# 20160428.net
KiCad netlist of a schematic drawn in Altium Designer
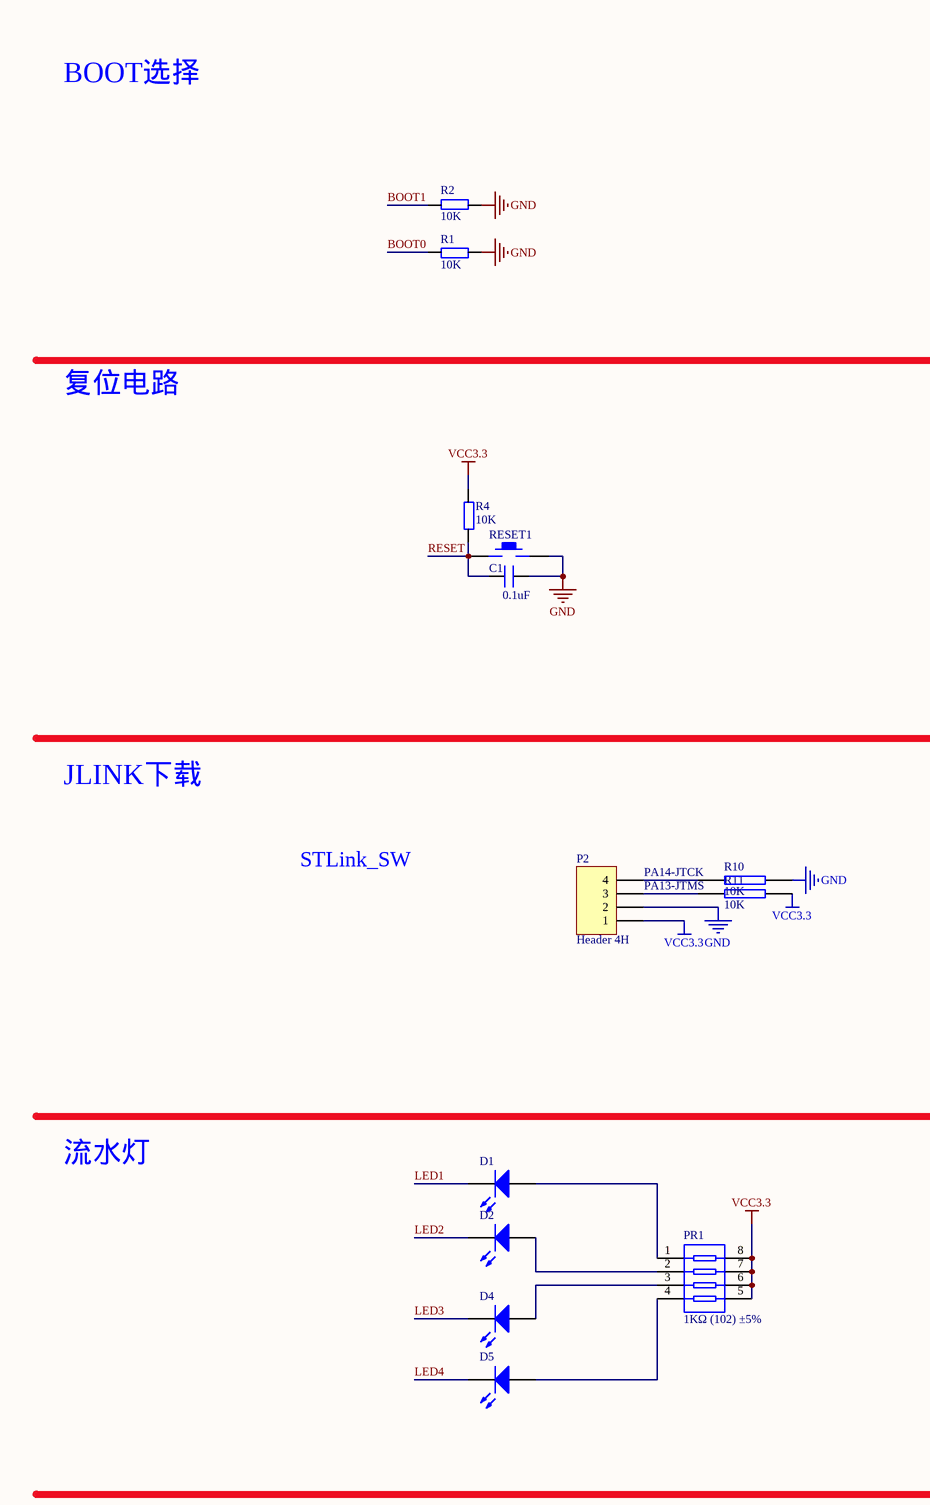
[diagram p0: 主控板20160428.SchDoc, top left]
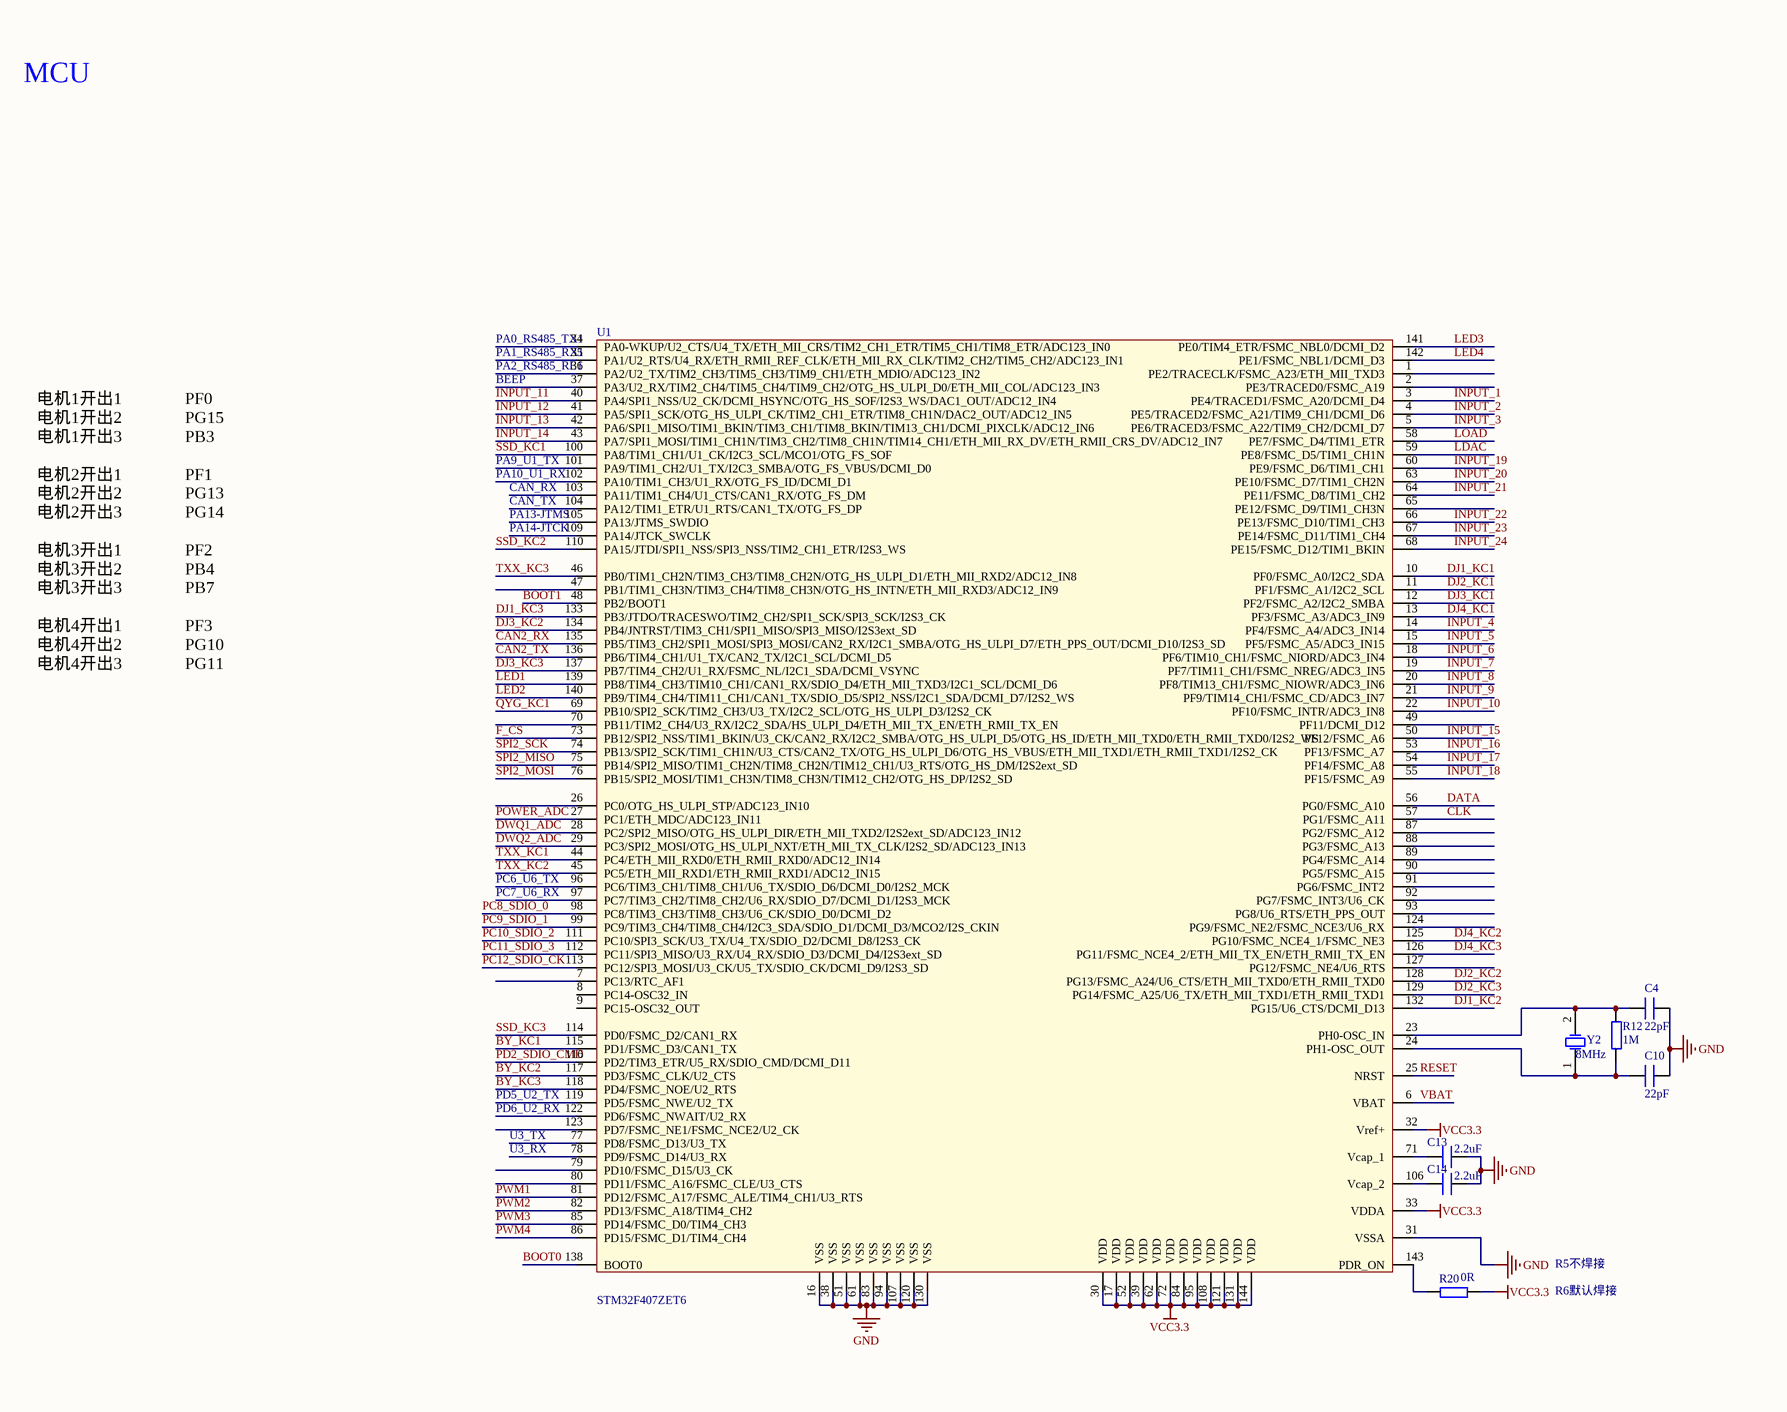
[diagram p1: 主控板20160428.SchDoc, top middle]
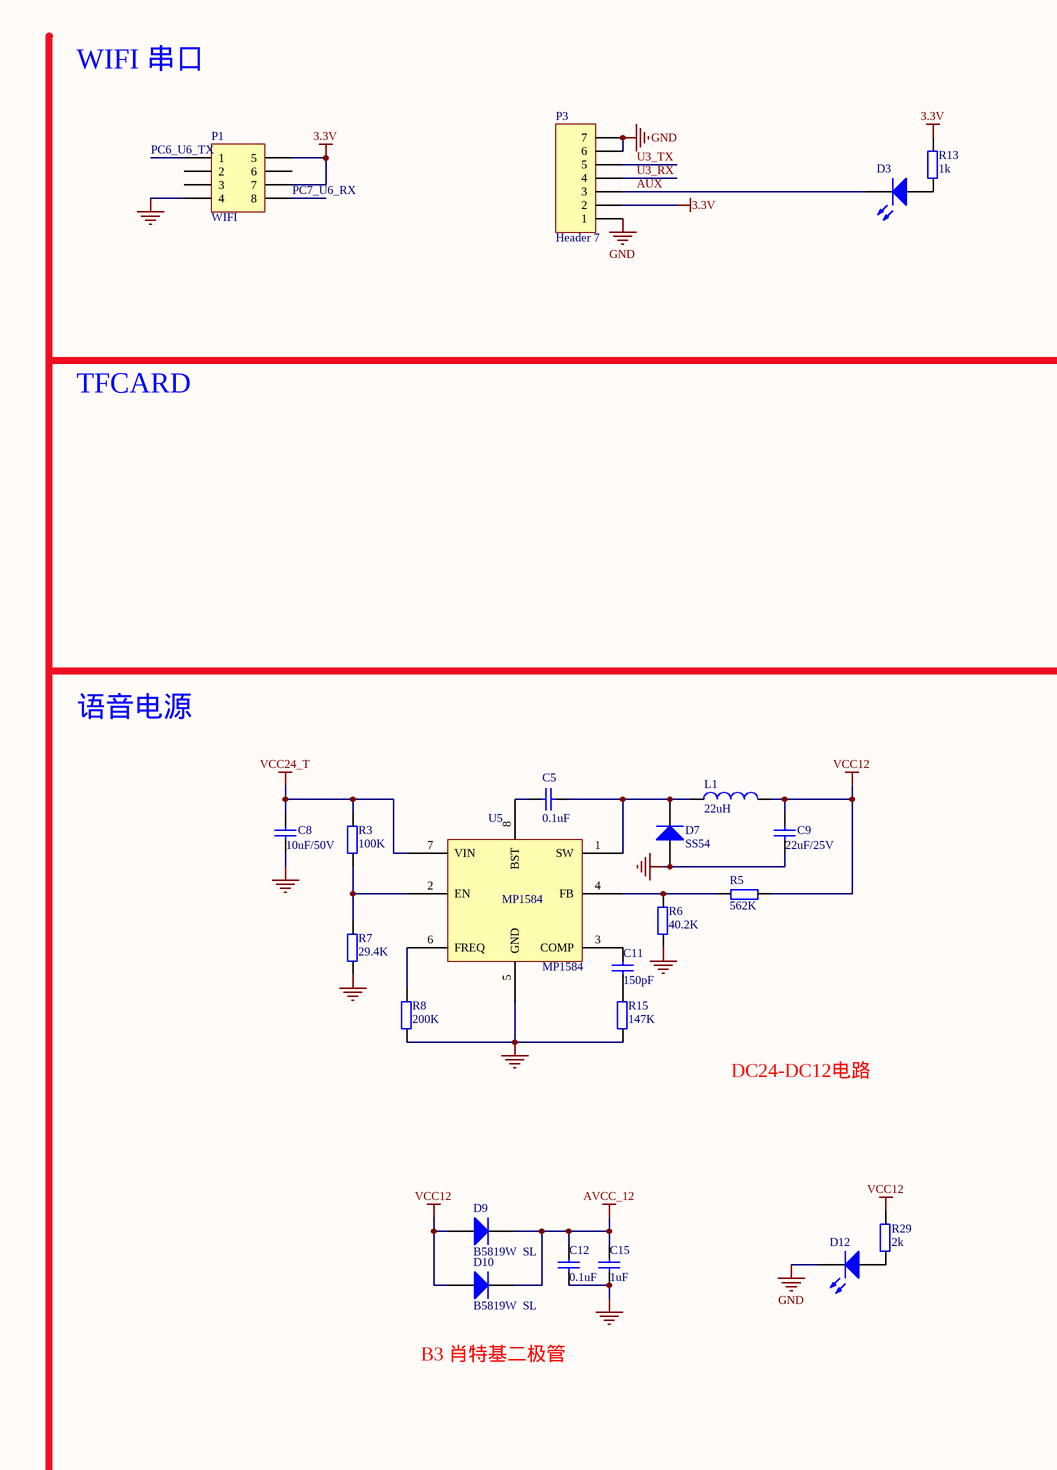
[diagram p2: 主控板20160428.SchDoc, top right]
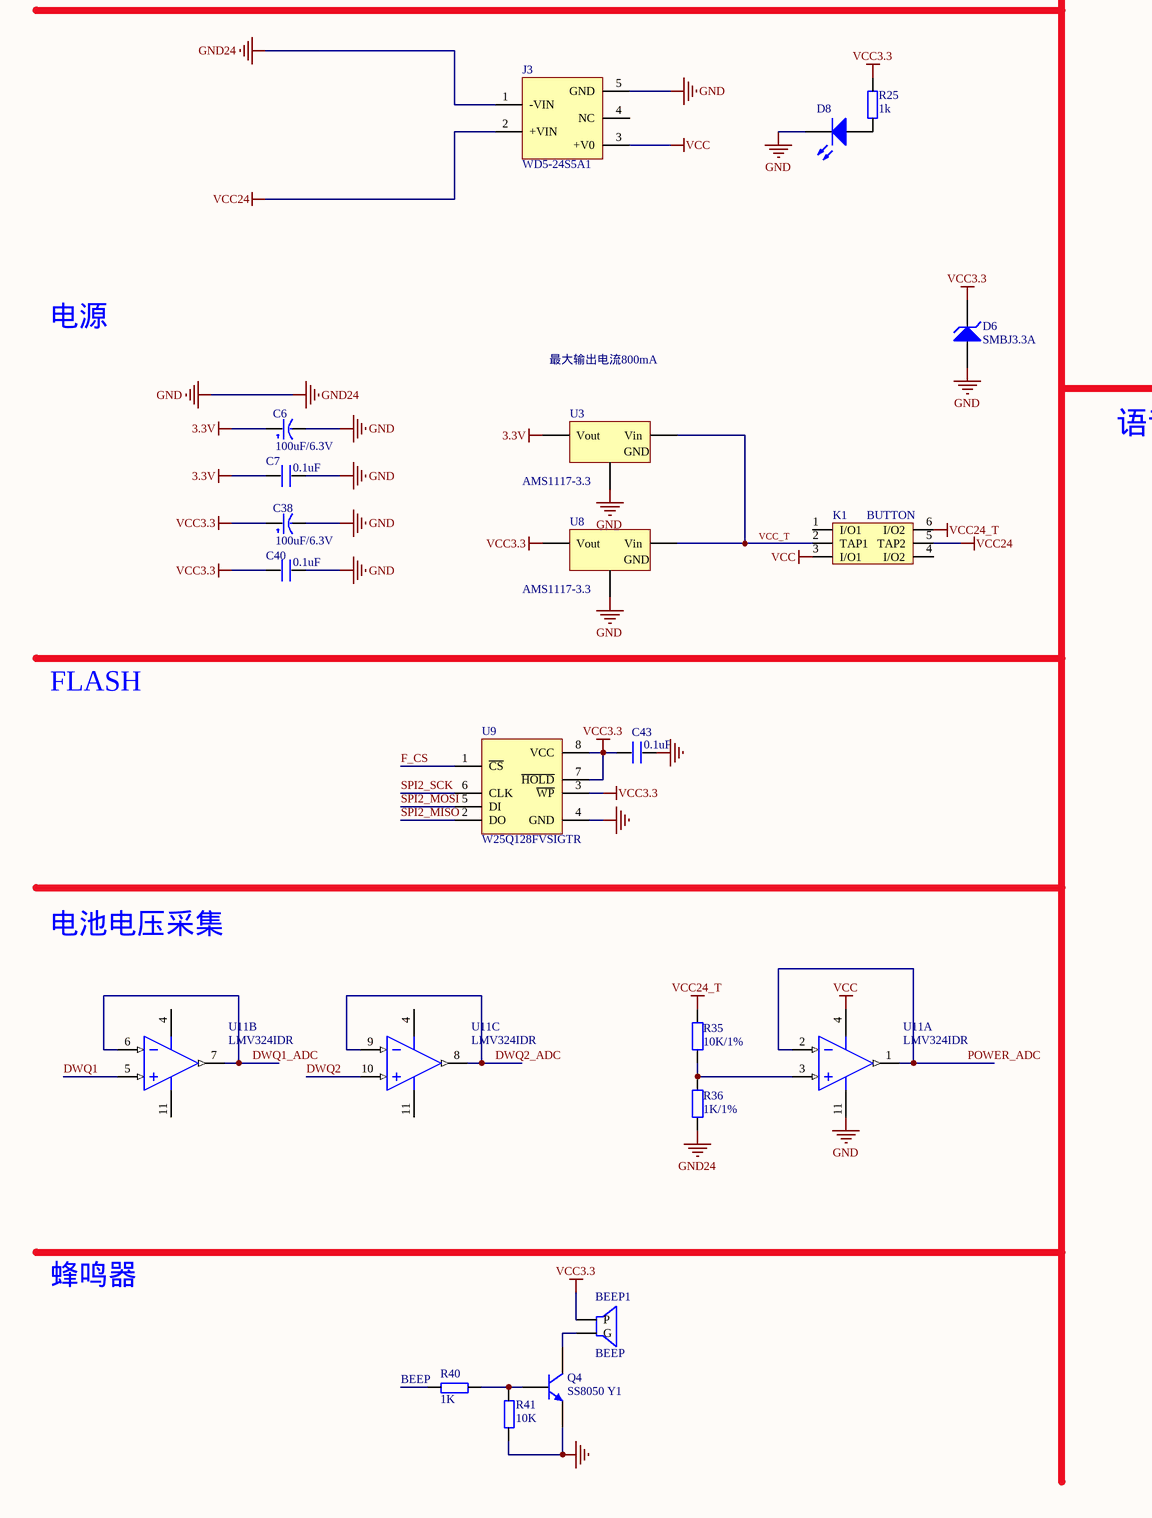
[diagram p3: 主控板20160428.SchDoc, bottom left]
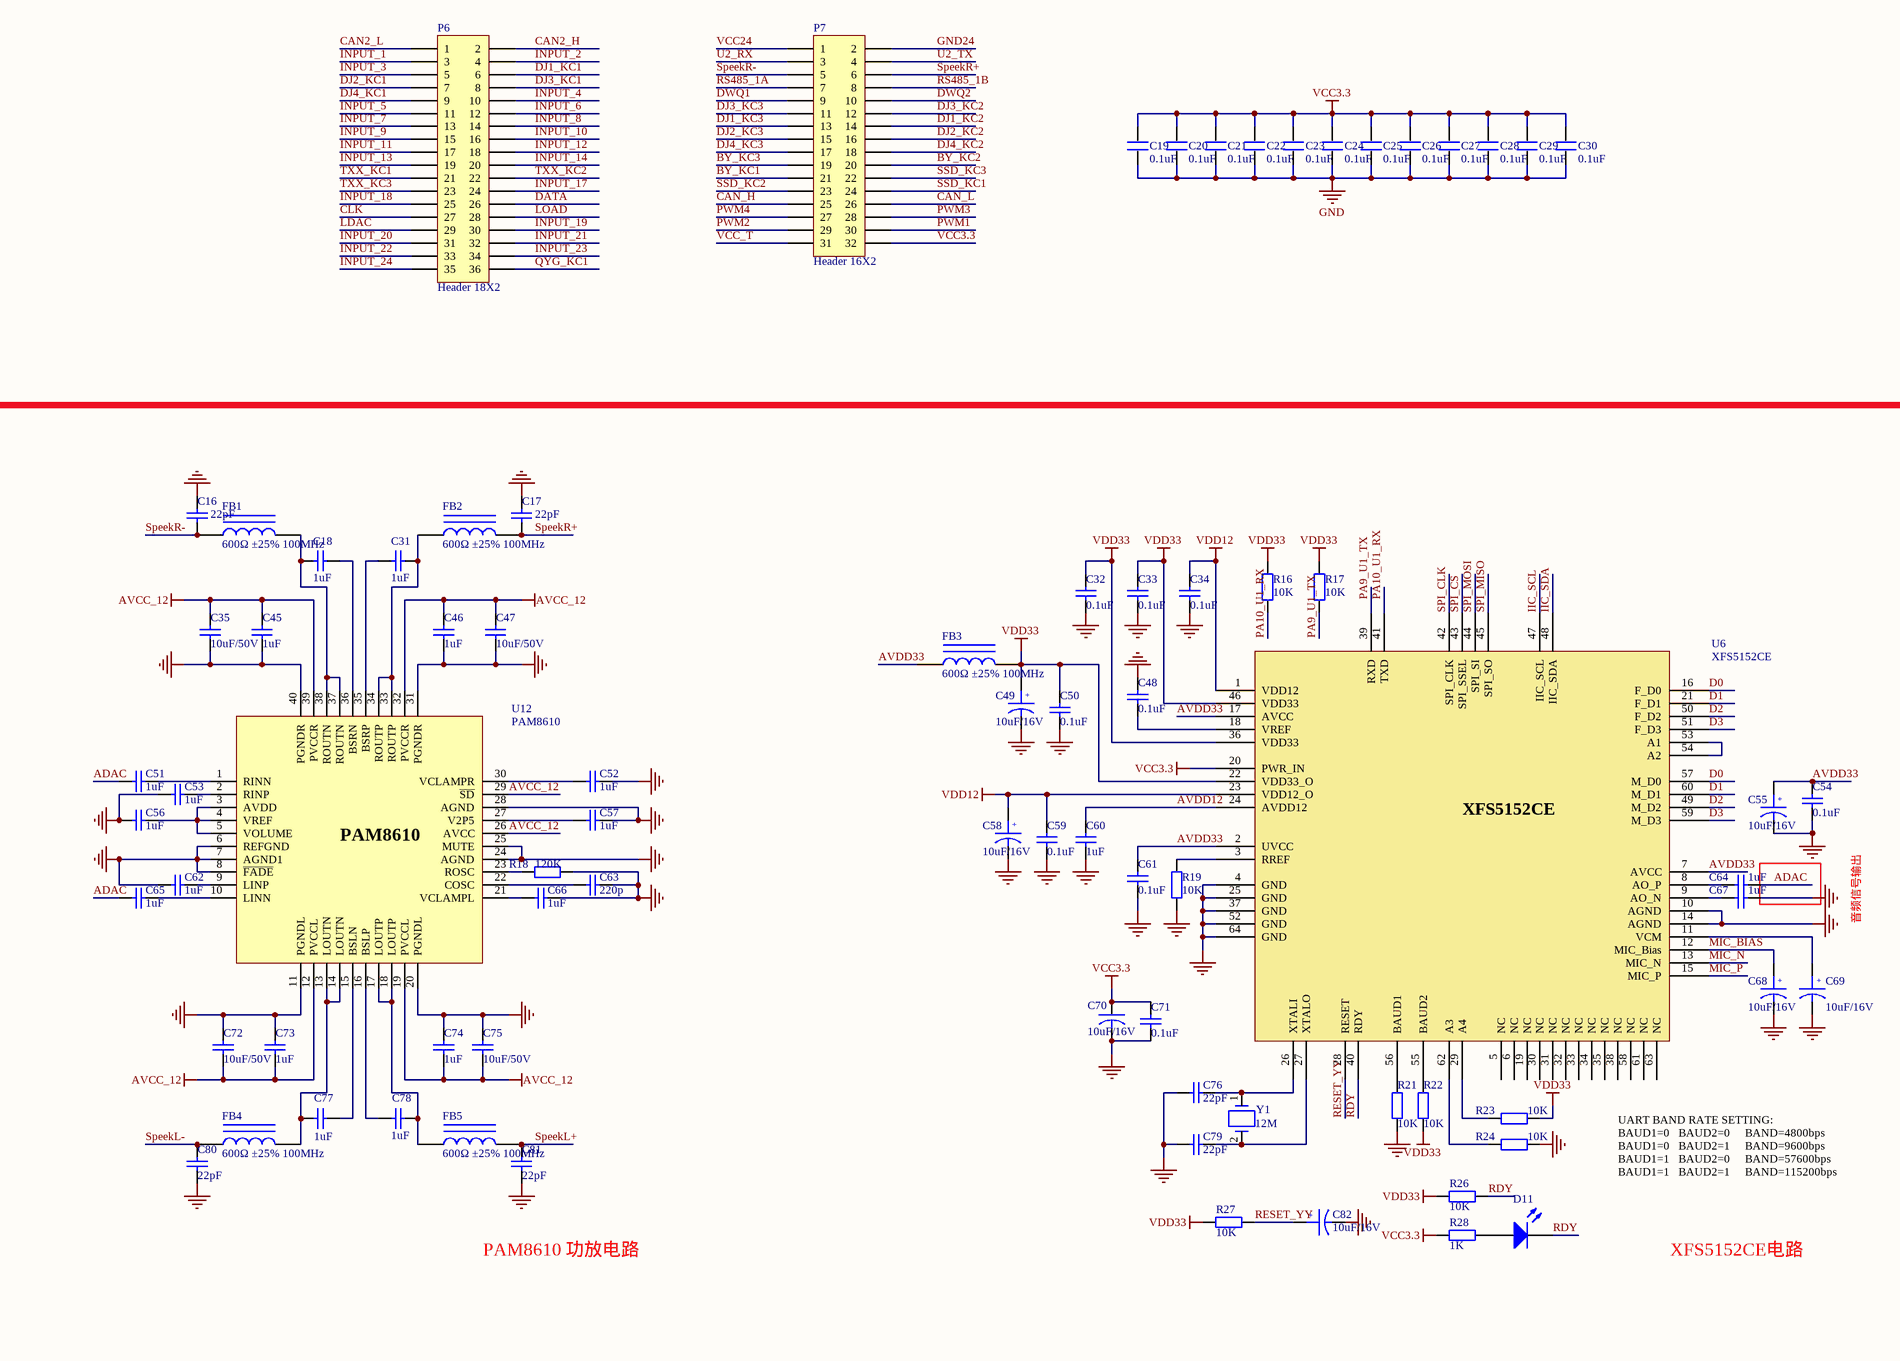
[diagram p4: 主控板20160428.SchDoc, bottom middle]
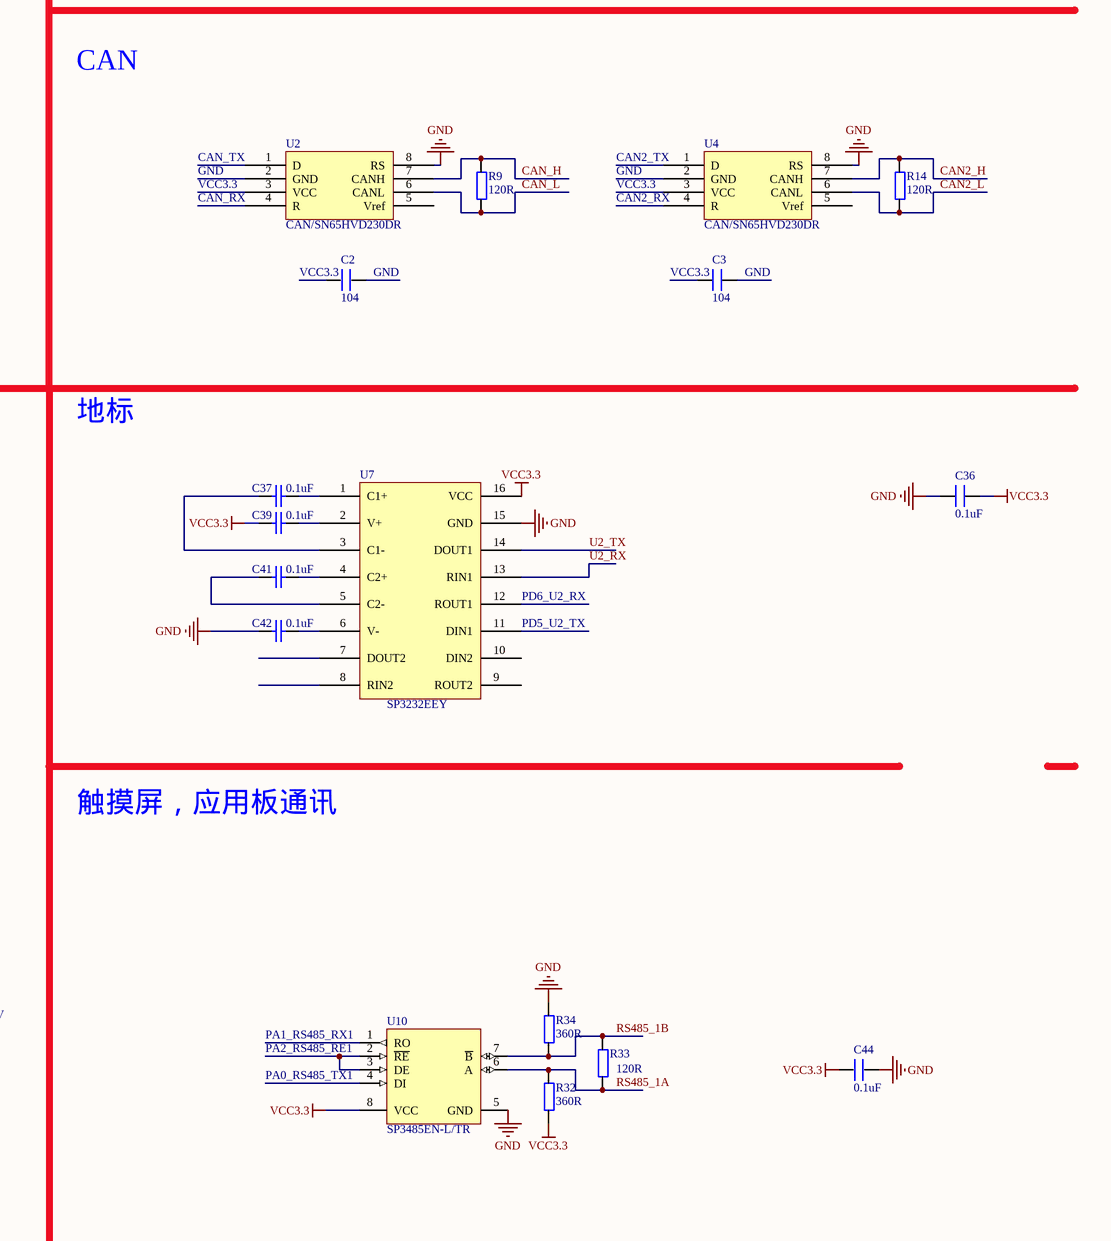
[diagram p5: 主控板20160428.SchDoc, bottom right]

(export (version "E")
  (design (tool "Eeschema 10.0.6"))
  (components
    (comp (ref "BEEP1") (value "BEEP") (footprint "BELL-5") (libsource (lib "WarShip V3_SCH") (part "BEEP")))
    (comp (ref "C1") (value "0.1uF") (footprint "C0805") (libsource (lib "Explorer STM32F407封装库") (part "C")))
    (comp (ref "C2") (value "104") (footprint "C0805") (libsource (lib "Explorer STM32F407封装库") (part "C_3")))
    (comp (ref "C3") (value "104") (footprint "C0805") (libsource (lib "Explorer STM32F407封装库") (part "C_3")))
    (comp (ref "C4")
      (value "22pF")
      (footprint "C0805")
      (libsource (lib "Explorer STM32F407封装库") (part "C_3"))
    )
    (comp (ref "C5")
      (value "0.1uF")
      (footprint "0603_C")
      (description "Capacitor (Semiconductor SIM Model)")
      (fields (field (name "PUBLISHER") "Altium Limited"))
      (libsource (lib "Miscellaneous Devices") (part "Cap Semi"))
    )
    (comp (ref "C6")
      (value "100uF/6.3V")
      (footprint "CASE-B_3528")
      (libsource (lib "WarShip V3_SCH") (part "CAP"))
    )
    (comp (ref "C7") (value "0.1uF") (footprint "C0805") (libsource (lib "WarShip V3_SCH") (part "C")))
    (comp (ref "C8")
      (value "10uF/50V")
      (footprint "1206_C")
      (description "Capacitor (Semiconductor SIM Model)")
      (fields (field (name "PUBLISHER") "Altium Limited"))
      (libsource (lib "Miscellaneous Devices") (part "Cap Semi"))
    )
    (comp (ref "C9")
      (value "22uF/25V")
      (footprint "0805_C")
      (description "Capacitor (Semiconductor SIM Model)")
      (fields (field (name "PUBLISHER") "Altium Limited"))
      (libsource (lib "Miscellaneous Devices") (part "Cap Semi"))
    )
    (comp (ref "C10")
      (value "22pF")
      (footprint "C0805")
      (libsource (lib "Explorer STM32F407封装库") (part "C_3"))
    )
    (comp (ref "C11")
      (value "150pF")
      (footprint "0603_C")
      (description "Capacitor (Semiconductor SIM Model)")
      (fields (field (name "PUBLISHER") "Altium Limited"))
      (libsource (lib "Miscellaneous Devices") (part "Cap Semi"))
    )
    (comp (ref "C12")
      (value "0.1uF")
      (footprint "0603_C")
      (description "Capacitor (Semiconductor SIM Model)")
      (fields (field (name "PUBLISHER") "Altium Limited"))
      (libsource (lib "Miscellaneous Devices") (part "Cap Semi"))
    )
    (comp (ref "C13")
      (value "2.2uF")
      (footprint "C0805")
      (libsource (lib "Explorer STM32F407封装库") (part "C"))
    )
    (comp (ref "C14")
      (value "2.2uF")
      (footprint "C0805")
      (libsource (lib "Explorer STM32F407封装库") (part "C"))
    )
    (comp (ref "C15")
      (value "1uF")
      (footprint "0603_C")
      (description "Capacitor (Semiconductor SIM Model)")
      (fields (field (name "PUBLISHER") "Altium Limited"))
      (libsource (lib "Miscellaneous Devices") (part "Cap Semi"))
    )
    (comp (ref "C16")
      (value "22pF")
      (footprint "0603_C")
      (description "Capacitor (Semiconductor SIM Model)")
      (fields (field (name "PUBLISHER") "Altium Limited"))
      (libsource (lib "Miscellaneous Devices") (part "Cap Semi"))
    )
    (comp (ref "C17")
      (value "22pF")
      (footprint "0603_C")
      (description "Capacitor (Semiconductor SIM Model)")
      (fields (field (name "PUBLISHER") "Altium Limited"))
      (libsource (lib "Miscellaneous Devices") (part "Cap Semi"))
    )
    (comp (ref "C18")
      (value "1uF")
      (footprint "0603_C")
      (description "Capacitor (Semiconductor SIM Model)")
      (fields (field (name "PUBLISHER") "Altium Limited"))
      (libsource (lib "Miscellaneous Devices") (part "Cap Semi"))
    )
    (comp (ref "C19") (value "0.1uF") (footprint "C0805") (libsource (lib "WarShip V3_SCH") (part "C")))
    (comp (ref "C20") (value "0.1uF") (footprint "C0805") (libsource (lib "WarShip V3_SCH") (part "C")))
    (comp (ref "C21") (value "0.1uF") (footprint "C0805") (libsource (lib "WarShip V3_SCH") (part "C")))
    (comp (ref "C22") (value "0.1uF") (footprint "C0805") (libsource (lib "WarShip V3_SCH") (part "C")))
    (comp (ref "C23") (value "0.1uF") (footprint "C0805") (libsource (lib "WarShip V3_SCH") (part "C")))
    (comp (ref "C24") (value "0.1uF") (footprint "C0805") (libsource (lib "WarShip V3_SCH") (part "C")))
    (comp (ref "C25") (value "0.1uF") (footprint "C0805") (libsource (lib "WarShip V3_SCH") (part "C")))
    (comp (ref "C26") (value "0.1uF") (footprint "C0805") (libsource (lib "WarShip V3_SCH") (part "C")))
    (comp (ref "C27") (value "0.1uF") (footprint "C0805") (libsource (lib "WarShip V3_SCH") (part "C")))
    (comp (ref "C28") (value "0.1uF") (footprint "C0805") (libsource (lib "WarShip V3_SCH") (part "C")))
    (comp (ref "C29") (value "0.1uF") (footprint "C0805") (libsource (lib "WarShip V3_SCH") (part "C")))
    (comp (ref "C30") (value "0.1uF") (footprint "C0805") (libsource (lib "WarShip V3_SCH") (part "C")))
    (comp (ref "C31")
      (value "1uF")
      (footprint "0603_C")
      (description "Capacitor (Semiconductor SIM Model)")
      (fields (field (name "PUBLISHER") "Altium Limited"))
      (libsource (lib "Miscellaneous Devices") (part "Cap Semi"))
    )
    (comp (ref "C32")
      (value "0.1uF")
      (footprint "0603_C")
      (description "Capacitor (Semiconductor SIM Model)")
      (fields (field (name "PUBLISHER") "Altium Limited"))
      (libsource (lib "Miscellaneous Devices") (part "Cap Semi"))
    )
    (comp (ref "C33")
      (value "0.1uF")
      (footprint "0603_C")
      (description "Capacitor (Semiconductor SIM Model)")
      (fields (field (name "PUBLISHER") "Altium Limited"))
      (libsource (lib "Miscellaneous Devices") (part "Cap Semi"))
    )
    (comp (ref "C34")
      (value "0.1uF")
      (footprint "0603_C")
      (description "Capacitor (Semiconductor SIM Model)")
      (fields (field (name "PUBLISHER") "Altium Limited"))
      (libsource (lib "Miscellaneous Devices") (part "Cap Semi"))
    )
    (comp (ref "C35")
      (value "10uF/50V")
      (footprint "1206_C")
      (description "电容")
      (fields (field (name "PUBLISHER") "Altium Limited"))
      (libsource (lib "*") (part "Cap NP"))
    )
    (comp (ref "C36")
      (value "0.1uF")
      (footprint "C0805")
      (libsource (lib "Explorer STM32F407封装库") (part "C_2"))
    )
    (comp (ref "C37")
      (value "0.1uF")
      (footprint "C0805")
      (description "Capacitor")
      (fields (field (name "PUBLISHER") "Altium Limited"))
      (libsource (lib "Miscellaneous Devices") (part "Cap"))
    )
    (comp (ref "C38")
      (value "100uF/6.3V")
      (footprint "CASE-B_3528")
      (libsource (lib "WarShip V3_SCH") (part "CAP"))
    )
    (comp (ref "C39")
      (value "0.1uF")
      (footprint "C0805")
      (description "Capacitor")
      (fields (field (name "PUBLISHER") "Altium Limited"))
      (libsource (lib "Miscellaneous Devices") (part "Cap"))
    )
    (comp (ref "C40") (value "0.1uF") (footprint "C0805") (libsource (lib "WarShip V3_SCH") (part "C")))
    (comp (ref "C41")
      (value "0.1uF")
      (footprint "C0805")
      (description "Capacitor")
      (fields (field (name "PUBLISHER") "Altium Limited"))
      (libsource (lib "Miscellaneous Devices") (part "Cap"))
    )
    (comp (ref "C42")
      (value "0.1uF")
      (footprint "C0805")
      (description "Capacitor")
      (fields (field (name "PUBLISHER") "Altium Limited"))
      (libsource (lib "Miscellaneous Devices") (part "Cap"))
    )
    (comp (ref "C43") (value "0.1uF") (footprint "C0805") (libsource (lib "WarShip V3_SCH") (part "C")))
    (comp (ref "C44")
      (value "0.1uF")
      (footprint "C0805")
      (libsource (lib "Explorer STM32F407封装库") (part "C_3"))
    )
    (comp (ref "C45")
      (value "1uF")
      (footprint "0603_C")
      (description "Capacitor (Semiconductor SIM Model)")
      (fields (field (name "PUBLISHER") "Altium Limited"))
      (libsource (lib "Miscellaneous Devices") (part "Cap Semi"))
    )
    (comp (ref "C46")
      (value "1uF")
      (footprint "0603_C")
      (description "Capacitor (Semiconductor SIM Model)")
      (fields (field (name "PUBLISHER") "Altium Limited"))
      (libsource (lib "Miscellaneous Devices") (part "Cap Semi"))
    )
    (comp (ref "C47")
      (value "10uF/50V")
      (footprint "1206_C")
      (description "电容")
      (fields (field (name "PUBLISHER") "Altium Limited"))
      (libsource (lib "*") (part "Cap NP"))
    )
    (comp (ref "C48")
      (value "0.1uF")
      (footprint "0603_C")
      (description "Capacitor (Semiconductor SIM Model)")
      (fields (field (name "PUBLISHER") "Altium Limited"))
      (libsource (lib "Miscellaneous Devices") (part "Cap Semi"))
    )
    (comp (ref "C49") (value "10uF/16V") (footprint "3216") (libsource (lib "*") (part "CAP POL")))
    (comp (ref "C50")
      (value "0.1uF")
      (footprint "0603_C")
      (description "Capacitor (Semiconductor SIM Model)")
      (fields (field (name "PUBLISHER") "Altium Limited"))
      (libsource (lib "Miscellaneous Devices") (part "Cap Semi"))
    )
    (comp (ref "C51")
      (value "1uF")
      (footprint "0603_C")
      (description "Capacitor (Semiconductor SIM Model)")
      (fields (field (name "PUBLISHER") "Altium Limited"))
      (libsource (lib "Miscellaneous Devices") (part "Cap Semi"))
    )
    (comp (ref "C52")
      (value "1uF")
      (footprint "0603_C")
      (description "Capacitor (Semiconductor SIM Model)")
      (fields (field (name "PUBLISHER") "Altium Limited"))
      (libsource (lib "Miscellaneous Devices") (part "Cap Semi"))
    )
    (comp (ref "C53")
      (value "1uF")
      (footprint "0603_C")
      (description "Capacitor (Semiconductor SIM Model)")
      (fields (field (name "PUBLISHER") "Altium Limited"))
      (libsource (lib "Miscellaneous Devices") (part "Cap Semi"))
    )
    (comp (ref "C54")
      (value "0.1uF")
      (footprint "0603_C")
      (description "Capacitor (Semiconductor SIM Model)")
      (fields (field (name "PUBLISHER") "Altium Limited"))
      (libsource (lib "Miscellaneous Devices") (part "Cap Semi"))
    )
    (comp (ref "C55") (value "10uF/16V") (footprint "3216") (libsource (lib "*") (part "CAP POL")))
    (comp (ref "C56")
      (value "1uF")
      (footprint "0603_C")
      (description "Capacitor (Semiconductor SIM Model)")
      (fields (field (name "PUBLISHER") "Altium Limited"))
      (libsource (lib "Miscellaneous Devices") (part "Cap Semi"))
    )
    (comp (ref "C57")
      (value "1uF")
      (footprint "0603_C")
      (description "Capacitor (Semiconductor SIM Model)")
      (fields (field (name "PUBLISHER") "Altium Limited"))
      (libsource (lib "Miscellaneous Devices") (part "Cap Semi"))
    )
    (comp (ref "C58") (value "10uF/16V") (footprint "3216") (libsource (lib "*") (part "CAP POL")))
    (comp (ref "C59")
      (value "0.1uF")
      (footprint "0603_C")
      (description "Capacitor (Semiconductor SIM Model)")
      (fields (field (name "PUBLISHER") "Altium Limited"))
      (libsource (lib "Miscellaneous Devices") (part "Cap Semi"))
    )
    (comp (ref "C60")
      (value "1uF")
      (footprint "0603_C")
      (description "Capacitor (Semiconductor SIM Model)")
      (fields (field (name "PUBLISHER") "Altium Limited"))
      (libsource (lib "Miscellaneous Devices") (part "Cap Semi"))
    )
    (comp (ref "C61")
      (value "0.1uF")
      (footprint "0603_C")
      (description "Capacitor (Semiconductor SIM Model)")
      (fields (field (name "PUBLISHER") "Altium Limited"))
      (libsource (lib "Miscellaneous Devices") (part "Cap Semi"))
    )
    (comp (ref "C62")
      (value "1uF")
      (footprint "0603_C")
      (description "Capacitor (Semiconductor SIM Model)")
      (fields (field (name "PUBLISHER") "Altium Limited"))
      (libsource (lib "Miscellaneous Devices") (part "Cap Semi"))
    )
    (comp (ref "C63")
      (value "220p")
      (footprint "0603_C")
      (description "Capacitor (Semiconductor SIM Model)")
      (fields (field (name "PUBLISHER") "Altium Limited"))
      (libsource (lib "Miscellaneous Devices") (part "Cap Semi"))
    )
    (comp (ref "C64")
      (value "1uF")
      (footprint "0603_C")
      (description "Capacitor (Semiconductor SIM Model)")
      (fields (field (name "PUBLISHER") "Altium Limited"))
      (libsource (lib "Miscellaneous Devices") (part "Cap Semi"))
    )
    (comp (ref "C65")
      (value "1uF")
      (footprint "0603_C")
      (description "Capacitor (Semiconductor SIM Model)")
      (fields (field (name "PUBLISHER") "Altium Limited"))
      (libsource (lib "Miscellaneous Devices") (part "Cap Semi"))
    )
    (comp (ref "C66")
      (value "1uF")
      (footprint "0603_C")
      (description "Capacitor (Semiconductor SIM Model)")
      (fields (field (name "PUBLISHER") "Altium Limited"))
      (libsource (lib "Miscellaneous Devices") (part "Cap Semi"))
    )
    (comp (ref "C67")
      (value "1uF")
      (footprint "0603_C")
      (description "Capacitor (Semiconductor SIM Model)")
      (fields (field (name "PUBLISHER") "Altium Limited"))
      (libsource (lib "Miscellaneous Devices") (part "Cap Semi"))
    )
    (comp (ref "C68") (value "10uF/16V") (footprint "3216") (libsource (lib "*") (part "CAP POL")))
    (comp (ref "C69") (value "10uF/16V") (footprint "3216") (libsource (lib "*") (part "CAP POL")))
    (comp (ref "C70")
      (value "10uF/16V")
      (footprint "3216")
      (description "Capacitor")
      (libsource (lib "*") (part "CAPACITOR"))
    )
    (comp (ref "C71")
      (value "0.1uF")
      (footprint "0603_C")
      (description "Capacitor (Semiconductor SIM Model)")
      (fields (field (name "PUBLISHER") "Altium Limited"))
      (libsource (lib "Miscellaneous Devices") (part "Cap Semi"))
    )
    (comp (ref "C72")
      (value "10uF/50V")
      (footprint "1206_C")
      (description "电容")
      (fields (field (name "PUBLISHER") "Altium Limited"))
      (libsource (lib "*") (part "Cap NP"))
    )
    (comp (ref "C73")
      (value "1uF")
      (footprint "0603_C")
      (description "Capacitor (Semiconductor SIM Model)")
      (fields (field (name "PUBLISHER") "Altium Limited"))
      (libsource (lib "Miscellaneous Devices") (part "Cap Semi"))
    )
    (comp (ref "C74")
      (value "1uF")
      (footprint "0603_C")
      (description "Capacitor (Semiconductor SIM Model)")
      (fields (field (name "PUBLISHER") "Altium Limited"))
      (libsource (lib "Miscellaneous Devices") (part "Cap Semi"))
    )
    (comp (ref "C75")
      (value "10uF/50V")
      (footprint "1206_C")
      (description "电容")
      (fields (field (name "PUBLISHER") "Altium Limited"))
      (libsource (lib "*") (part "Cap NP"))
    )
    (comp (ref "C76")
      (value "22pF")
      (footprint "0603_C")
      (description "电容")
      (fields (field (name "PUBLISHER") "Altium Limited"))
      (libsource (lib "*") (part "Cap NP"))
    )
    (comp (ref "C77")
      (value "1uF")
      (footprint "0603_C")
      (description "Capacitor (Semiconductor SIM Model)")
      (fields (field (name "PUBLISHER") "Altium Limited"))
      (libsource (lib "Miscellaneous Devices") (part "Cap Semi"))
    )
    (comp (ref "C78")
      (value "1uF")
      (footprint "0603_C")
      (description "Capacitor (Semiconductor SIM Model)")
      (fields (field (name "PUBLISHER") "Altium Limited"))
      (libsource (lib "Miscellaneous Devices") (part "Cap Semi"))
    )
    (comp (ref "C79")
      (value "22pF")
      (footprint "0603_C")
      (description "电容")
      (fields (field (name "PUBLISHER") "Altium Limited"))
      (libsource (lib "*") (part "Cap NP"))
    )
    (comp (ref "C80")
      (value "22pF")
      (footprint "0603_C")
      (description "Capacitor (Semiconductor SIM Model)")
      (fields (field (name "PUBLISHER") "Altium Limited"))
      (libsource (lib "Miscellaneous Devices") (part "Cap Semi"))
    )
    (comp (ref "C81")
      (value "22pF")
      (footprint "0603_C")
      (description "Capacitor (Semiconductor SIM Model)")
      (fields (field (name "PUBLISHER") "Altium Limited"))
      (libsource (lib "Miscellaneous Devices") (part "Cap Semi"))
    )
    (comp (ref "C82") (value "10uF/16V") (footprint "3216") (libsource (lib "*") (part "CAP POL")))
    (comp (ref "D1")
      (value "红灯 0805")
      (footprint "LC-0805_LED_S1")
      (description "Typical INFRARED GaAs LED")
      (fields (field (name "PUBLISHER") "Altium Limited"))
      (libsource (lib "继电器板_1") (part "LED0"))
    )
    (comp (ref "D2")
      (value "红灯 0805")
      (footprint "LC-0805_LED_S1")
      (description "Typical INFRARED GaAs LED")
      (fields (field (name "PUBLISHER") "Altium Limited"))
      (libsource (lib "继电器板_1") (part "LED0"))
    )
    (comp (ref "D3")
      (value "红灯 0805")
      (footprint "LC-0805_LED_S1")
      (description "Typical INFRARED GaAs LED")
      (fields (field (name "PUBLISHER") "Altium Limited"))
      (libsource (lib "继电器板_1") (part "LED0"))
    )
    (comp (ref "D4")
      (value "红灯 0805")
      (footprint "LC-0805_LED_S1")
      (description "Typical INFRARED GaAs LED")
      (fields (field (name "PUBLISHER") "Altium Limited"))
      (libsource (lib "继电器板_1") (part "LED0"))
    )
    (comp (ref "D5")
      (value "红灯 0805")
      (footprint "LC-0805_LED_S1")
      (description "Typical INFRARED GaAs LED")
      (fields (field (name "PUBLISHER") "Altium Limited"))
      (libsource (lib "继电器板_1") (part "LED0"))
    )
    (comp (ref "D6")
      (value "SMBJ3.3A")
      (footprint "SMB(DO-214AA)_S1")
      (description "Zener Diode")
      (fields (field (name "PUBLISHER") "Altium Limited"))
      (libsource (lib "Miscellaneous Devices") (part "D Zener"))
    )
    (comp (ref "D7")
      (value "SS54")
      (footprint "SMA(DO-214AC)_S1")
      (description "二极管")
      (libsource (lib "Miscellaneous Devices LC") (part "SMA(DO-214AC) SS54"))
    )
    (comp (ref "D8")
      (value "蓝灯 0805")
      (footprint "LC-0805_LED_S1")
      (description "Typical INFRARED GaAs LED")
      (fields (field (name "PUBLISHER") "Altium Limited"))
      (libsource (lib "继电器板_1") (part "LED0"))
    )
    (comp (ref "D9")
      (value "B5819W  SL")
      (footprint "SOD-123")
      (description "肖特基二极管")
      (libsource (lib "Miscellaneous Devices LC") (part "SOD-123 B5819W  SL"))
    )
    (comp (ref "D10")
      (value "B5819W  SL")
      (footprint "SOD-123")
      (description "肖特基二极管")
      (libsource (lib "Miscellaneous Devices LC") (part "SOD-123 B5819W  SL"))
    )
    (comp (ref "D11")
      (value "红灯 0805")
      (footprint "LC-0805_LED_S1")
      (description "Typical INFRARED GaAs LED")
      (fields (field (name "PUBLISHER") "Altium Limited"))
      (libsource (lib "继电器板_1") (part "LED0"))
    )
    (comp (ref "D12")
      (value "蓝灯 0805")
      (footprint "LC-0805_LED_S1")
      (description "Typical INFRARED GaAs LED")
      (fields (field (name "PUBLISHER") "Altium Limited"))
      (libsource (lib "继电器板_1") (part "LED0"))
    )
    (comp (ref "FB1")
      (value "600Ω ±25% 100MHz")
      (footprint "0805_L")
      (description "贴片磁珠")
      (libsource (lib "Miscellaneous Devices LC") (part "0805 600Ω 25% 100MHz"))
    )
    (comp (ref "FB2")
      (value "600Ω ±25% 100MHz")
      (footprint "0805_L")
      (description "贴片磁珠")
      (libsource (lib "Miscellaneous Devices LC") (part "0805 600Ω 25% 100MHz"))
    )
    (comp (ref "FB3")
      (value "600Ω ±25% 100MHz")
      (footprint "0805_L")
      (description "贴片磁珠")
      (libsource (lib "Miscellaneous Devices LC") (part "0805 600Ω 25% 100MHz"))
    )
    (comp (ref "FB4")
      (value "600Ω ±25% 100MHz")
      (footprint "0805_L")
      (description "贴片磁珠")
      (libsource (lib "Miscellaneous Devices LC") (part "0805 600Ω 25% 100MHz"))
    )
    (comp (ref "FB5")
      (value "600Ω ±25% 100MHz")
      (footprint "0805_L")
      (description "贴片磁珠")
      (libsource (lib "Miscellaneous Devices LC") (part "0805 600Ω 25% 100MHz"))
    )
    (comp (ref "J3")
      (value "WD5-24S5A1")
      (footprint "WD5-24S3V3")
      (libsource (lib "*") (part "WD5-24S3V3A1"))
    )
    (comp (ref "K1")
      (value "BUTTON")
      (footprint "BTN8.5*8.5")
      (libsource (lib "WarShip V3_SCH") (part "BUTTON"))
    )
    (comp (ref "L1")
      (value "22uH")
      (footprint "L-7*7*4mm-S")
      (description "Inductor")
      (fields (field (name "PUBLISHER") "Altium Limited"))
      (libsource (lib "Miscellaneous Devices") (part "Inductor"))
    )
    (comp (ref "P1")
      (value "WIFI")
      (footprint "HDR2X4_CEN")
      (description "Header, 4-Pin, Dual row")
      (fields (field (name "PUBLISHER") "Altium Limited"))
      (libsource (lib "Miscellaneous Connectors") (part "Header 4X2A"))
    )
    (comp (ref "P2")
      (value "Header 4H")
      (footprint "IDE4")
      (description "Header, 4-Pin, Right Angle")
      (fields (field (name "PUBLISHER") "Altium Limited"))
      (libsource (lib "Miscellaneous Connectors") (part "Header 4H"))
    )
    (comp (ref "P3")
      (value "Header 7")
      (footprint "AS50-T27")
      (description "Header, 7-Pin")
      (fields (field (name "PUBLISHER") "Altium Limited"))
      (libsource (lib "Miscellaneous Connectors") (part "Header 7"))
    )
    (comp (ref "P6")
      (value "Header 18X2")
      (footprint "HDR2X18")
      (description "Header, 18-Pin, Dual row")
      (fields (field (name "PUBLISHER") "Altium Limited"))
      (libsource (lib "Miscellaneous Connectors") (part "Header 18X2"))
    )
    (comp (ref "P7")
      (value "Header 16X2")
      (footprint "HDR2X16")
      (description "Header, 16-Pin, Dual row")
      (fields (field (name "PUBLISHER") "Altium Limited"))
      (libsource (lib "Miscellaneous Connectors") (part "Header 16X2"))
    )
    (comp (ref "PR1")
      (value "1KΩ (102) ±5%")
      (footprint "0603_Rx4")
      (description "贴片排阻")
      (libsource (lib "Miscellaneous Devices LC") (part "0603*4  1KΩ (102) 5%"))
    )
    (comp (ref "Q4")
      (value "SS8050 Y1")
      (footprint "SOT-23(SOT-23-3)")
      (description "三极管")
      (libsource (lib "Miscellaneous Devices LC") (part "SOT-23 SS8050 Y1"))
    )
    (comp (ref "R1")
      (value "10K")
      (footprint "0805_R")
      (libsource (lib "Explorer STM32F407封装库") (part "R_1"))
    )
    (comp (ref "R2")
      (value "10K")
      (footprint "0805_R")
      (libsource (lib "Explorer STM32F407封装库") (part "R_1"))
    )
    (comp (ref "R3")
      (value "100K")
      (footprint "0603_R")
      (libsource (lib "Explorer STM32F407封装库") (part "R_2"))
    )
    (comp (ref "R4")
      (value "10K")
      (footprint "0805_R")
      (libsource (lib "Explorer STM32F407封装库") (part "R_2"))
    )
    (comp (ref "R5")
      (value "562K")
      (footprint "0603_R")
      (libsource (lib "Explorer STM32F407封装库") (part "R_2"))
    )
    (comp (ref "R6")
      (value "40.2K")
      (footprint "0603_R")
      (libsource (lib "Explorer STM32F407封装库") (part "R_2"))
    )
    (comp (ref "R7")
      (value "29.4K")
      (footprint "0603_R")
      (libsource (lib "Explorer STM32F407封装库") (part "R_2"))
    )
    (comp (ref "R8")
      (value "200K")
      (footprint "0603_R")
      (libsource (lib "Explorer STM32F407封装库") (part "R_2"))
    )
    (comp (ref "R9")
      (value "120R")
      (footprint "0805_R")
      (libsource (lib "Explorer STM32F407封装库") (part "R_2"))
    )
    (comp (ref "R10") (value "10K") (footprint "0805_R") (libsource (lib "*") (part "RES2")))
    (comp (ref "R11") (value "10K") (footprint "0805_R") (libsource (lib "*") (part "RES2")))
    (comp (ref "R12") (value "1M") (footprint "0805_R") (libsource (lib "Explorer STM32F407封装库") (part "R")))
    (comp (ref "R13")
      (value "1k")
      (footprint "0805_R")
      (libsource (lib "Explorer STM32F407封装库") (part "R_2"))
    )
    (comp (ref "R14")
      (value "120R")
      (footprint "0805_R")
      (libsource (lib "Explorer STM32F407封装库") (part "R_2"))
    )
    (comp (ref "R15")
      (value "147K")
      (footprint "0603_R")
      (libsource (lib "Explorer STM32F407封装库") (part "R_2"))
    )
    (comp (ref "R16")
      (value "10K")
      (footprint "0603_R")
      (description "Resistor")
      (fields (field (name "PUBLISHER") "Altium Limited"))
      (libsource (lib "") (part "Res2_2"))
    )
    (comp (ref "R17")
      (value "10K")
      (footprint "0603_R")
      (description "Resistor")
      (fields (field (name "PUBLISHER") "Altium Limited"))
      (libsource (lib "") (part "Res2_1"))
    )
    (comp (ref "R18")
      (value "120K")
      (footprint "0603_R")
      (description "Resistor")
      (fields (field (name "PUBLISHER") "Altium Limited"))
      (libsource (lib "") (part "Res2_3"))
    )
    (comp (ref "R19")
      (value "10K")
      (footprint "0603_R")
      (description "Resistor")
      (fields (field (name "PUBLISHER") "Altium Limited"))
      (libsource (lib "") (part "Res2_2"))
    )
    (comp (ref "R20")
      (value "0R")
      (footprint "0805_R")
      (libsource (lib "Explorer STM32F407封装库") (part "R_2"))
    )
    (comp (ref "R21")
      (value "10K")
      (footprint "0603_R")
      (description "Resistor")
      (fields (field (name "PUBLISHER") "Altium Limited"))
      (libsource (lib "") (part "Res2_1"))
    )
    (comp (ref "R22")
      (value "10K")
      (footprint "0603_R")
      (description "Resistor")
      (fields (field (name "PUBLISHER") "Altium Limited"))
      (libsource (lib "") (part "Res2_1"))
    )
    (comp (ref "R23")
      (value "10K")
      (footprint "0603_R")
      (description "Resistor")
      (fields (field (name "PUBLISHER") "Altium Limited"))
      (libsource (lib "*") (part "Res2"))
    )
    (comp (ref "R24")
      (value "10K")
      (footprint "0603_R")
      (description "Resistor")
      (fields (field (name "PUBLISHER") "Altium Limited"))
      (libsource (lib "") (part "Res2_3"))
    )
    (comp (ref "R25")
      (value "1k")
      (footprint "0805_R")
      (libsource (lib "Explorer STM32F407封装库") (part "R_2"))
    )
    (comp (ref "R26")
      (value "10K")
      (footprint "0603_R")
      (description "Resistor")
      (fields (field (name "PUBLISHER") "Altium Limited"))
      (libsource (lib "*") (part "Res2"))
    )
    (comp (ref "R27")
      (value "10K")
      (footprint "0603_R")
      (description "Resistor")
      (fields (field (name "PUBLISHER") "Altium Limited"))
      (libsource (lib "*") (part "Res2"))
    )
    (comp (ref "R28")
      (value "1K")
      (footprint "0603_R")
      (description "Resistor")
      (fields (field (name "PUBLISHER") "Altium Limited"))
      (libsource (lib "*") (part "Res2"))
    )
    (comp (ref "R29")
      (value "2k")
      (footprint "0603_R")
      (libsource (lib "Explorer STM32F407封装库") (part "R_2"))
    )
    (comp (ref "R32")
      (value "360R")
      (footprint "0603_R")
      (libsource (lib "Explorer STM32F407封装库") (part "R_2"))
    )
    (comp (ref "R33")
      (value "120R")
      (footprint "0805_R")
      (libsource (lib "Explorer STM32F407封装库") (part "R_2"))
    )
    (comp (ref "R34")
      (value "360R")
      (footprint "0603_R")
      (libsource (lib "Explorer STM32F407封装库") (part "R_2"))
    )
    (comp (ref "R35")
      (value "10K/1%")
      (footprint "0805_R")
      (description "Resistor")
      (fields (field (name "PUBLISHER") "Altium Limited"))
      (libsource (lib "Miscellaneous Devices") (part "Res2"))
    )
    (comp (ref "R36")
      (value "1K/1%")
      (footprint "0805_R")
      (description "Resistor")
      (fields (field (name "PUBLISHER") "Altium Limited"))
      (libsource (lib "Miscellaneous Devices") (part "Res2"))
    )
    (comp (ref "R40") (value "1K") (footprint "0805_R") (libsource (lib "WarShip V3_SCH") (part "R")))
    (comp (ref "R41") (value "10K") (footprint "0805_R") (libsource (lib "WarShip V3_SCH") (part "R")))
    (comp (ref "RESET1")
      (value "KEY_M")
      (footprint "SW_PB2_A1")
      (libsource (lib "Explorer STM32F407封装库") (part "KEY_M"))
    )
    (comp (ref "U1")
      (value "STM32F407ZET6")
      (footprint "LQFP144")
      (libsource (lib "Explorer STM32F407封装库") (part "STM32F407ZET6"))
    )
    (comp (ref "U2")
      (value "CAN/SN65HVD230DR")
      (footprint "SOIC-8_150mil")
      (description "CAN")
      (libsource (lib "Miscellaneous Devices LC") (part "CAN/SN65HVD230DR"))
    )
    (comp (ref "U3")
      (value "AMS1117-3.3")
      (footprint "SOT-223")
      (description "低压差线性稳压(LDO)")
      (libsource (lib "Miscellaneous Devices LC") (part "SOT-223 AMS1117-3.3"))
    )
    (comp (ref "U4")
      (value "CAN/SN65HVD230DR")
      (footprint "SOIC-8_150mil")
      (description "CAN")
      (libsource (lib "Miscellaneous Devices LC") (part "CAN/SN65HVD230DR"))
    )
    (comp (ref "U5")
      (value "MP1584")
      (footprint "LC-SOIC-8_EP_150MIL")
      (libsource (lib "磁导航") (part "MP1584EN"))
    )
    (comp (ref "U6")
      (value "XFS5152CE")
      (footprint "LQFP-64_10x10x05P")
      (libsource (lib "*") (part "XFS5152-2"))
    )
    (comp (ref "U7")
      (value "SP3232EEY")
      (footprint "TSSOP-16")
      (description "RS232")
      (libsource (lib "Smart_board_v1") (part "MAX3232CUE"))
    )
    (comp (ref "U8")
      (value "AMS1117-3.3")
      (footprint "SOT-223")
      (description "低压差线性稳压(LDO)")
      (libsource (lib "Miscellaneous Devices LC") (part "SOT-223 AMS1117-3.3"))
    )
    (comp (ref "U9")
      (value "W25Q128FVSIGTR")
      (footprint "SOIC8_W")
      (description "Flash ROM")
      (libsource (lib "fszhang") (part "W25QXX"))
    )
    (comp (ref "U10")
      (value "SP3485EN-L/TR")
      (footprint "SOIC-8_150mil")
      (description "RS-485/RS-422")
      (libsource (lib "Miscellaneous Devices LC") (part "SP3485EN-L/TR"))
    )
    (comp (ref "U11")
      (value "LMV324IDR")
      (footprint "SOIC-14_150mil")
      (description "运放")
      (libsource (lib "Miscellaneous Devices LC") (part "LMV324IDR"))
    )
    (comp (ref "U12")
      (value "PAM8610")
      (footprint "QFN50P600X600X80-40N")
      (libsource (lib "my third") (part "PAM8610功放芯片"))
    )
    (comp (ref "Y1")
      (value "12M")
      (footprint "XTAL_US")
      (description "晶振")
      (libsource (lib "*") (part "XTAL1"))
    )
    (comp (ref "Y2")
      (value "8MHz")
      (footprint "XTAL_US")
      (description "Crystal Oscillator")
      (fields (field (name "PUBLISHER") "Altium Limited"))
      (libsource (lib "Explorer STM32F407封装库") (part "XTAL"))
    )
  )
  (nets
    (net (code "1") (name "/ADAC") (class "Default")
      (node (ref "C51") (pin "1") (pinfunction "1_1") (pintype "passive"))
      (node (ref "C64") (pin "1") (pinfunction "1_1") (pintype "passive"))
      (node (ref "C65") (pin "1") (pinfunction "1_1") (pintype "passive"))
    )
    (net (code "2") (name "/AUX") (class "Default")
      (node (ref "D3") (pin "K") (pinfunction "K_K") (pintype "passive"))
      (node (ref "P3") (pin "3") (pinfunction "3_3") (pintype "passive"))
    )
    (net (code "3") (name "/AVDD12") (class "Default")
      (node (ref "C60") (pin "2") (pinfunction "2_2") (pintype "passive"))
      (node (ref "U6") (pin "24") (pinfunction "AVDD12_24") (pintype "passive"))
    )
    (net (code "4") (name "/AVDD33") (class "Default")
      (node (ref "C54") (pin "1") (pinfunction "1_1") (pintype "passive"))
      (node (ref "C55") (pin "1") (pinfunction "1_1") (pintype "passive"))
      (node (ref "C61") (pin "1") (pinfunction "1_1") (pintype "passive"))
      (node (ref "FB3") (pin "1") (pinfunction "1_1") (pintype "passive"))
      (node (ref "U6") (pin "17") (pinfunction "AVCC_17") (pintype "passive"))
      (node (ref "U6") (pin "2") (pinfunction "UVCC_2") (pintype "passive"))
      (node (ref "U6") (pin "7") (pinfunction "AVCC_7") (pintype "passive"))
    )
    (net (code "5") (name "/BEEP") (class "Default")
      (node (ref "R40") (pin "1") (pintype "passive"))
      (node (ref "U1") (pin "37") (pinfunction "PA3/U2_RX/TIM2_CH4/TIM5_CH4/TIM9_CH2/OTG_HS_ULPI_D0/ETH_MII_COL/ADC123_IN3_37") (pintype "passive"))
    )
    (net (code "6") (name "/BOOT0") (class "Default")
      (node (ref "R1") (pin "1") (pintype "passive"))
      (node (ref "U1") (pin "138") (pinfunction "BOOT0_138") (pintype "passive"))
    )
    (net (code "7") (name "/BOOT1") (class "Default")
      (node (ref "R2") (pin "2") (pintype "passive"))
      (node (ref "U1") (pin "48") (pinfunction "PB2/BOOT1_48") (pintype "passive"))
    )
    (net (code "8") (name "/BY_KC1") (class "Default")
      (node (ref "P7") (pin "21") (pinfunction "21_21") (pintype "passive"))
      (node (ref "U1") (pin "115") (pinfunction "PD1/FSMC_D3/CAN1_TX_115") (pintype "passive"))
    )
    (net (code "9") (name "/BY_KC2") (class "Default")
      (node (ref "P7") (pin "20") (pinfunction "20_20") (pintype "passive"))
      (node (ref "U1") (pin "117") (pinfunction "PD3/FSMC_CLK/U2_CTS_117") (pintype "passive"))
    )
    (net (code "10") (name "/BY_KC3") (class "Default")
      (node (ref "P7") (pin "19") (pinfunction "19_19") (pintype "passive"))
      (node (ref "U1") (pin "118") (pinfunction "PD4/FSMC_NOE/U2_RTS_118") (pintype "passive"))
    )
    (net (code "11") (name "/CAN2_H") (class "Default")
      (node (ref "P6") (pin "2") (pinfunction "2_2") (pintype "passive"))
      (node (ref "R14") (pin "2") (pintype "passive"))
      (node (ref "U4") (pin "7") (pinfunction "CANH_7") (pintype "passive"))
    )
    (net (code "12") (name "/CAN2_L") (class "Default")
      (node (ref "P6") (pin "1") (pinfunction "1_1") (pintype "passive"))
      (node (ref "R14") (pin "1") (pintype "passive"))
      (node (ref "U4") (pin "6") (pinfunction "CANL_6") (pintype "passive"))
    )
    (net (code "13") (name "/CAN2_RX") (class "Default")
      (node (ref "U1") (pin "135") (pinfunction "PB5/TIM3_CH2/SPI1_MOSI/SPI3_MOSI/CAN2_RX/I2C1_SMBA/OTG_HS_ULPI_D7/ETH_PPS_OUT/DCMI_D10/I2S3_SD_135") (pintype "passive"))
      (node (ref "U4") (pin "4") (pinfunction "R_4") (pintype "passive"))
    )
    (net (code "14") (name "/CAN2_TX") (class "Default")
      (node (ref "U1") (pin "136") (pinfunction "PB6/TIM4_CH1/U1_TX/CAN2_TX/I2C1_SCL/DCMI_D5_136") (pintype "passive"))
      (node (ref "U4") (pin "1") (pinfunction "D_1") (pintype "passive"))
    )
    (net (code "15") (name "/CAN_H") (class "Default")
      (node (ref "P7") (pin "25") (pinfunction "25_25") (pintype "passive"))
      (node (ref "R9") (pin "2") (pintype "passive"))
      (node (ref "U2") (pin "7") (pinfunction "CANH_7") (pintype "passive"))
    )
    (net (code "16") (name "/CAN_L") (class "Default")
      (node (ref "P7") (pin "26") (pinfunction "26_26") (pintype "passive"))
      (node (ref "R9") (pin "1") (pintype "passive"))
      (node (ref "U2") (pin "6") (pinfunction "CANL_6") (pintype "passive"))
    )
    (net (code "17") (name "/CAN_RX") (class "Default")
      (node (ref "U1") (pin "103") (pinfunction "PA11/TIM1_CH4/U1_CTS/CAN1_RX/OTG_FS_DM_103") (pintype "passive"))
      (node (ref "U2") (pin "4") (pinfunction "R_4") (pintype "passive"))
    )
    (net (code "18") (name "/CAN_TX") (class "Default")
      (node (ref "U1") (pin "104") (pinfunction "PA12/TIM1_ETR/U1_RTS/CAN1_TX/OTG_FS_DP_104") (pintype "passive"))
      (node (ref "U2") (pin "1") (pinfunction "D_1") (pintype "passive"))
    )
    (net (code "19") (name "/CLK") (class "Default")
      (node (ref "P6") (pin "27") (pinfunction "27_27") (pintype "passive"))
      (node (ref "U1") (pin "57") (pinfunction "PG1/FSMC_A11_57") (pintype "passive"))
    )
    (net (code "20") (name "/D0") (class "Default")
      (node (ref "U6") (pin "16") (pinfunction "F_D0_16") (pintype "passive"))
      (node (ref "U6") (pin "57") (pinfunction "M_D0_57") (pintype "passive"))
    )
    (net (code "21") (name "/D1") (class "Default")
      (node (ref "U6") (pin "21") (pinfunction "F_D1_21") (pintype "passive"))
      (node (ref "U6") (pin "60") (pinfunction "M_D1_60") (pintype "passive"))
    )
    (net (code "22") (name "/D2") (class "Default")
      (node (ref "U6") (pin "49") (pinfunction "M_D2_49") (pintype "passive"))
      (node (ref "U6") (pin "50") (pinfunction "F_D2_50") (pintype "passive"))
    )
    (net (code "23") (name "/D3") (class "Default")
      (node (ref "U6") (pin "51") (pinfunction "F_D3_51") (pintype "passive"))
      (node (ref "U6") (pin "59") (pinfunction "M_D3_59") (pintype "passive"))
    )
    (net (code "24") (name "/DATA") (class "Default")
      (node (ref "P6") (pin "26") (pinfunction "26_26") (pintype "passive"))
      (node (ref "U1") (pin "56") (pinfunction "PG0/FSMC_A10_56") (pintype "passive"))
    )
    (net (code "25") (name "/DJ1_KC1") (class "Default")
      (node (ref "P6") (pin "6") (pinfunction "6_6") (pintype "passive"))
      (node (ref "U1") (pin "10") (pinfunction "PF0/FSMC_A0/I2C2_SDA_10") (pintype "passive"))
    )
    (net (code "26") (name "/DJ1_KC2") (class "Default")
      (node (ref "P7") (pin "14") (pinfunction "14_14") (pintype "passive"))
      (node (ref "U1") (pin "132") (pinfunction "PG15/U6_CTS/DCMI_D13_132") (pintype "passive"))
    )
    (net (code "27") (name "/DJ1_KC3") (class "Default")
      (node (ref "P7") (pin "13") (pinfunction "13_13") (pintype "passive"))
      (node (ref "U1") (pin "133") (pinfunction "PB3/JTDO/TRACESWO/TIM2_CH2/SPI1_SCK/SPI3_SCK/I2S3_CK_133") (pintype "passive"))
    )
    (net (code "28") (name "/DJ2_KC1") (class "Default")
      (node (ref "P6") (pin "7") (pinfunction "7_7") (pintype "passive"))
      (node (ref "U1") (pin "11") (pinfunction "PF1/FSMC_A1/I2C2_SCL_11") (pintype "passive"))
    )
    (net (code "29") (name "/DJ2_KC2") (class "Default")
      (node (ref "P7") (pin "16") (pinfunction "16_16") (pintype "passive"))
      (node (ref "U1") (pin "128") (pinfunction "PG13/FSMC_A24/U6_CTS/ETH_MII_TXD0/ETH_RMII_TXD0_128") (pintype "passive"))
    )
    (net (code "30") (name "/DJ2_KC3") (class "Default")
      (node (ref "P7") (pin "15") (pinfunction "15_15") (pintype "passive"))
      (node (ref "U1") (pin "129") (pinfunction "PG14/FSMC_A25/U6_TX/ETH_MII_TXD1/ETH_RMII_TXD1_129") (pintype "passive"))
    )
    (net (code "31") (name "/DJ3_KC1") (class "Default")
      (node (ref "P6") (pin "8") (pinfunction "8_8") (pintype "passive"))
      (node (ref "U1") (pin "12") (pinfunction "PF2/FSMC_A2/I2C2_SMBA_12") (pintype "passive"))
    )
    (net (code "32") (name "/DJ3_KC2") (class "Default")
      (node (ref "P7") (pin "12") (pinfunction "12_12") (pintype "passive"))
      (node (ref "U1") (pin "134") (pinfunction "PB4/JNTRST/TIM3_CH1/SPI1_MISO/SPI3_MISO/I2S3ext_SD_134") (pintype "passive"))
    )
    (net (code "33") (name "/DJ3_KC3") (class "Default")
      (node (ref "P7") (pin "11") (pinfunction "11_11") (pintype "passive"))
      (node (ref "U1") (pin "137") (pinfunction "PB7/TIM4_CH2/U1_RX/FSMC_NL/I2C1_SDA/DCMI_VSYNC_137") (pintype "passive"))
    )
    (net (code "34") (name "/DJ4_KC1") (class "Default")
      (node (ref "P6") (pin "9") (pinfunction "9_9") (pintype "passive"))
      (node (ref "U1") (pin "13") (pinfunction "PF3/FSMC_A3/ADC3_IN9_13") (pintype "passive"))
    )
    (net (code "35") (name "/DJ4_KC2") (class "Default")
      (node (ref "P7") (pin "18") (pinfunction "18_18") (pintype "passive"))
      (node (ref "U1") (pin "125") (pinfunction "PG10/FSMC_NCE4_1/FSMC_NE3_125") (pintype "passive"))
    )
    (net (code "36") (name "/DJ4_KC3") (class "Default")
      (node (ref "P7") (pin "17") (pinfunction "17_17") (pintype "passive"))
      (node (ref "U1") (pin "126") (pinfunction "PG11/FSMC_NCE4_2/ETH_MII_TX_EN/ETH_RMII_TX_EN_126") (pintype "passive"))
    )
    (net (code "37") (name "/DWQ1") (class "Default")
      (node (ref "P7") (pin "9") (pinfunction "9_9") (pintype "passive"))
      (node (ref "U11") (pin "5") (pinfunction "INB+_5") (pintype "input"))
    )
    (net (code "38") (name "/DWQ1_ADC") (class "Default")
      (node (ref "U1") (pin "28") (pinfunction "PC2/SPI2_MISO/OTG_HS_ULPI_DIR/ETH_MII_TXD2/I2S2ext_SD/ADC123_IN12_28") (pintype "passive"))
      (node (ref "U11") (pin "6") (pinfunction "INB-_6") (pintype "input"))
      (node (ref "U11") (pin "7") (pinfunction "OUTB_7") (pintype "output"))
    )
    (net (code "39") (name "/DWQ2") (class "Default")
      (node (ref "P7") (pin "10") (pinfunction "10_10") (pintype "passive"))
      (node (ref "U11") (pin "10") (pinfunction "INC+_10") (pintype "input"))
    )
    (net (code "40") (name "/DWQ2_ADC") (class "Default")
      (node (ref "U1") (pin "29") (pinfunction "PC3/SPI2_MOSI/OTG_HS_ULPI_NXT/ETH_MII_TX_CLK/I2S2_SD/ADC123_IN13_29") (pintype "passive"))
      (node (ref "U11") (pin "8") (pinfunction "OUTC_8") (pintype "output"))
      (node (ref "U11") (pin "9") (pinfunction "INC-_9") (pintype "input"))
    )
    (net (code "41") (name "/F_CS") (class "Default")
      (node (ref "U1") (pin "73") (pinfunction "PB12/SPI2_NSS/TIM1_BKIN/U3_CK/CAN2_RX/I2C2_SMBA/OTG_HS_ULPI_D5/OTG_HS_ID/ETH_MII_TXD0/ETH_RMII_TXD0/I2S2_WS_73") (pintype "passive"))
      (node (ref "U9") (pin "1") (pinfunction "~{CS}_1") (pintype "passive"))
    )
    (net (code "42") (name "/IIC_SCL") (class "Default")
      (node (ref "U6") (pin "47") (pinfunction "IIC_SCL_47") (pintype "passive"))
    )
    (net (code "43") (name "/IIC_SDA") (class "Default")
      (node (ref "U6") (pin "48") (pinfunction "IIC_SDA_48") (pintype "passive"))
    )
    (net (code "44") (name "/INPUT_1") (class "Default")
      (node (ref "P6") (pin "3") (pinfunction "3_3") (pintype "passive"))
      (node (ref "U1") (pin "3") (pinfunction "PE4/TRACED1/FSMC_A20/DCMI_D4_3") (pintype "passive"))
    )
    (net (code "45") (name "/INPUT_2") (class "Default")
      (node (ref "P6") (pin "4") (pinfunction "4_4") (pintype "passive"))
      (node (ref "U1") (pin "4") (pinfunction "PE5/TRACED2/FSMC_A21/TIM9_CH1/DCMI_D6_4") (pintype "passive"))
    )
    (net (code "46") (name "/INPUT_3") (class "Default")
      (node (ref "P6") (pin "5") (pinfunction "5_5") (pintype "passive"))
      (node (ref "U1") (pin "5") (pinfunction "PE6/TRACED3/FSMC_A22/TIM9_CH2/DCMI_D7_5") (pintype "passive"))
    )
    (net (code "47") (name "/INPUT_4") (class "Default")
      (node (ref "P6") (pin "10") (pinfunction "10_10") (pintype "passive"))
      (node (ref "U1") (pin "14") (pinfunction "PF4/FSMC_A4/ADC3_IN14_14") (pintype "passive"))
    )
    (net (code "48") (name "/INPUT_5") (class "Default")
      (node (ref "P6") (pin "11") (pinfunction "11_11") (pintype "passive"))
      (node (ref "U1") (pin "15") (pinfunction "PF5/FSMC_A5/ADC3_IN15_15") (pintype "passive"))
    )
    (net (code "49") (name "/INPUT_6") (class "Default")
      (node (ref "P6") (pin "12") (pinfunction "12_12") (pintype "passive"))
      (node (ref "U1") (pin "18") (pinfunction "PF6/TIM10_CH1/FSMC_NIORD/ADC3_IN4_18") (pintype "passive"))
    )
    (net (code "50") (name "/INPUT_7") (class "Default")
      (node (ref "P6") (pin "13") (pinfunction "13_13") (pintype "passive"))
      (node (ref "U1") (pin "19") (pinfunction "PF7/TIM11_CH1/FSMC_NREG/ADC3_IN5_19") (pintype "passive"))
    )
    (net (code "51") (name "/INPUT_8") (class "Default")
      (node (ref "P6") (pin "14") (pinfunction "14_14") (pintype "passive"))
      (node (ref "U1") (pin "20") (pinfunction "PF8/TIM13_CH1/FSMC_NIOWR/ADC3_IN6_20") (pintype "passive"))
    )
    (net (code "52") (name "/INPUT_9") (class "Default")
      (node (ref "P6") (pin "15") (pinfunction "15_15") (pintype "passive"))
      (node (ref "U1") (pin "21") (pinfunction "PF9/TIM14_CH1/FSMC_CD/ADC3_IN7_21") (pintype "passive"))
    )
    (net (code "53") (name "/INPUT_10") (class "Default")
      (node (ref "P6") (pin "16") (pinfunction "16_16") (pintype "passive"))
      (node (ref "U1") (pin "22") (pinfunction "PF10/FSMC_INTR/ADC3_IN8_22") (pintype "passive"))
    )
    (net (code "54") (name "/INPUT_11") (class "Default")
      (node (ref "P6") (pin "17") (pinfunction "17_17") (pintype "passive"))
      (node (ref "U1") (pin "40") (pinfunction "PA4/SPI1_NSS/U2_CK/DCMI_HSYNC/OTG_HS_SOF/I2S3_WS/DAC1_OUT/ADC12_IN4_40") (pintype "passive"))
    )
    (net (code "55") (name "/INPUT_12") (class "Default")
      (node (ref "P6") (pin "18") (pinfunction "18_18") (pintype "passive"))
      (node (ref "U1") (pin "41") (pinfunction "PA5/SPI1_SCK/OTG_HS_ULPI_CK/TIM2_CH1_ETR/TIM8_CH1N/DAC2_OUT/ADC12_IN5_41") (pintype "passive"))
    )
    (net (code "56") (name "/INPUT_13") (class "Default")
      (node (ref "P6") (pin "19") (pinfunction "19_19") (pintype "passive"))
      (node (ref "U1") (pin "42") (pinfunction "PA6/SPI1_MISO/TIM1_BKIN/TIM3_CH1/TIM8_BKIN/TIM13_CH1/DCMI_PIXCLK/ADC12_IN6_42") (pintype "passive"))
    )
    (net (code "57") (name "/INPUT_14") (class "Default")
      (node (ref "P6") (pin "20") (pinfunction "20_20") (pintype "passive"))
      (node (ref "U1") (pin "43") (pinfunction "PA7/SPI1_MOSI/TIM1_CH1N/TIM3_CH2/TIM8_CH1N/TIM14_CH1/ETH_MII_RX_DV/ETH_RMII_CRS_DV/ADC12_IN7_43") (pintype "passive"))
    )
    (net (code "58") (name "/INPUT_15") (class "Default")
      (node (ref "U1") (pin "50") (pinfunction "PF12/FSMC_A6_50") (pintype "passive"))
    )
    (net (code "59") (name "/INPUT_16") (class "Default")
      (node (ref "U1") (pin "53") (pinfunction "PF13/FSMC_A7_53") (pintype "passive"))
    )
    (net (code "60") (name "/INPUT_17") (class "Default")
      (node (ref "P6") (pin "24") (pinfunction "24_24") (pintype "passive"))
      (node (ref "U1") (pin "54") (pinfunction "PF14/FSMC_A8_54") (pintype "passive"))
    )
    (net (code "61") (name "/INPUT_18") (class "Default")
      (node (ref "P6") (pin "25") (pinfunction "25_25") (pintype "passive"))
      (node (ref "U1") (pin "55") (pinfunction "PF15/FSMC_A9_55") (pintype "passive"))
    )
    (net (code "62") (name "/INPUT_19") (class "Default")
      (node (ref "P6") (pin "30") (pinfunction "30_30") (pintype "passive"))
      (node (ref "U1") (pin "60") (pinfunction "PE9/FSMC_D6/TIM1_CH1_60") (pintype "passive"))
    )
    (net (code "63") (name "/INPUT_20") (class "Default")
      (node (ref "P6") (pin "31") (pinfunction "31_31") (pintype "passive"))
      (node (ref "U1") (pin "63") (pinfunction "PE10/FSMC_D7/TIM1_CH2N_63") (pintype "passive"))
    )
    (net (code "64") (name "/INPUT_21") (class "Default")
      (node (ref "P6") (pin "32") (pinfunction "32_32") (pintype "passive"))
      (node (ref "U1") (pin "64") (pinfunction "PE11/FSMC_D8/TIM1_CH2_64") (pintype "passive"))
    )
    (net (code "65") (name "/INPUT_22") (class "Default")
      (node (ref "P6") (pin "33") (pinfunction "33_33") (pintype "passive"))
      (node (ref "U1") (pin "66") (pinfunction "PE13/FSMC_D10/TIM1_CH3_66") (pintype "passive"))
    )
    (net (code "66") (name "/INPUT_23") (class "Default")
      (node (ref "P6") (pin "34") (pinfunction "34_34") (pintype "passive"))
      (node (ref "U1") (pin "67") (pinfunction "PE14/FSMC_D11/TIM1_CH4_67") (pintype "passive"))
    )
    (net (code "67") (name "/INPUT_24") (class "Default")
      (node (ref "P6") (pin "35") (pinfunction "35_35") (pintype "passive"))
      (node (ref "U1") (pin "68") (pinfunction "PE15/FSMC_D12/TIM1_BKIN_68") (pintype "passive"))
    )
    (net (code "68") (name "/LDAC") (class "Default")
      (node (ref "P6") (pin "29") (pinfunction "29_29") (pintype "passive"))
      (node (ref "U1") (pin "59") (pinfunction "PE8/FSMC_D5/TIM1_CH1N_59") (pintype "passive"))
    )
    (net (code "69") (name "/LED1") (class "Default")
      (node (ref "D1") (pin "K") (pinfunction "K_K") (pintype "passive"))
      (node (ref "U1") (pin "139") (pinfunction "PB8/TIM4_CH3/TIM10_CH1/CAN1_RX/SDIO_D4/ETH_MII_TXD3/I2C1_SCL/DCMI_D6_139") (pintype "passive"))
    )
    (net (code "70") (name "/LED2") (class "Default")
      (node (ref "D2") (pin "K") (pinfunction "K_K") (pintype "passive"))
      (node (ref "U1") (pin "140") (pinfunction "PB9/TIM4_CH4/TIM11_CH1/CAN1_TX/SDIO_D5/SPI2_NSS/I2C1_SDA/DCMI_D7/I2S2_WS_140") (pintype "passive"))
    )
    (net (code "71") (name "/LED3") (class "Default")
      (node (ref "D4") (pin "K") (pinfunction "K_K") (pintype "passive"))
      (node (ref "U1") (pin "141") (pinfunction "PE0/TIM4_ETR/FSMC_NBL0/DCMI_D2_141") (pintype "passive"))
    )
    (net (code "72") (name "/LED4") (class "Default")
      (node (ref "D5") (pin "K") (pinfunction "K_K") (pintype "passive"))
      (node (ref "U1") (pin "142") (pinfunction "PE1/FSMC_NBL1/DCMI_D3_142") (pintype "passive"))
    )
    (net (code "73") (name "/LOAD") (class "Default")
      (node (ref "P6") (pin "28") (pinfunction "28_28") (pintype "passive"))
      (node (ref "U1") (pin "58") (pinfunction "PE7/FSMC_D4/TIM1_ETR_58") (pintype "passive"))
    )
    (net (code "74") (name "/MIC_BIAS") (class "Default")
      (node (ref "C68") (pin "1") (pinfunction "1_1") (pintype "passive"))
      (node (ref "U6") (pin "12") (pinfunction "MIC_Bias_12") (pintype "passive"))
    )
    (net (code "75") (name "/MIC_N") (class "Default")
      (node (ref "U6") (pin "13") (pinfunction "MIC_N_13") (pintype "passive"))
    )
    (net (code "76") (name "/MIC_P") (class "Default")
      (node (ref "U6") (pin "15") (pinfunction "MIC_P_15") (pintype "passive"))
    )
    (net (code "77") (name "/PA0_RS485_TX1") (class "Default")
      (node (ref "U1") (pin "34") (pinfunction "PA0-WKUP/U2_CTS/U4_TX/ETH_MII_CRS/TIM2_CH1_ETR/TIM5_CH1/TIM8_ETR/ADC123_IN0_34") (pintype "passive"))
      (node (ref "U10") (pin "4") (pinfunction "DI_4") (pintype "input"))
    )
    (net (code "78") (name "/PA1_RS485_RX1") (class "Default")
      (node (ref "U1") (pin "35") (pinfunction "PA1/U2_RTS/U4_RX/ETH_RMII_REF_CLK/ETH_MII_RX_CLK/TIM2_CH2/TIM5_CH2/ADC123_IN1_35") (pintype "passive"))
      (node (ref "U10") (pin "1") (pinfunction "RO_1") (pintype "output"))
    )
    (net (code "79") (name "/PA2_RS485_RE1") (class "Default")
      (node (ref "U1") (pin "36") (pinfunction "PA2/U2_TX/TIM2_CH3/TIM5_CH3/TIM9_CH1/ETH_MDIO/ADC123_IN2_36") (pintype "passive"))
      (node (ref "U10") (pin "2") (pinfunction "~{RE}_2") (pintype "input"))
      (node (ref "U10") (pin "3") (pinfunction "DE_3") (pintype "input"))
    )
    (net (code "80") (name "/PA9_U1_TX") (class "Default")
      (node (ref "R17") (pin "2") (pinfunction "2_2") (pintype "passive"))
      (node (ref "U1") (pin "101") (pinfunction "PA9/TIM1_CH2/U1_TX/I2C3_SMBA/OTG_FS_VBUS/DCMI_D0_101") (pintype "passive"))
      (node (ref "U6") (pin "39") (pinfunction "RXD_39") (pintype "passive"))
    )
    (net (code "81") (name "/PA10_U1_RX") (class "Default")
      (node (ref "R16") (pin "1") (pinfunction "1_1") (pintype "passive"))
      (node (ref "U1") (pin "102") (pinfunction "PA10/TIM1_CH3/U1_RX/OTG_FS_ID/DCMI_D1_102") (pintype "passive"))
      (node (ref "U6") (pin "41") (pinfunction "TXD_41") (pintype "passive"))
    )
    (net (code "82") (name "/PA13-JTMS") (class "Default")
      (node (ref "P2") (pin "3") (pinfunction "3_3") (pintype "passive"))
      (node (ref "R11") (pin "2") (pinfunction "2_2") (pintype "passive"))
      (node (ref "U1") (pin "105") (pinfunction "PA13/JTMS_SWDIO_105") (pintype "passive"))
    )
    (net (code "83") (name "/PA14-JTCK") (class "Default")
      (node (ref "P2") (pin "4") (pinfunction "4_4") (pintype "passive"))
      (node (ref "R10") (pin "2") (pinfunction "2_2") (pintype "passive"))
      (node (ref "U1") (pin "109") (pinfunction "PA14/JTCK_SWCLK_109") (pintype "passive"))
    )
    (net (code "84") (name "/PC6_U6_TX") (class "Default")
      (node (ref "P1") (pin "1") (pinfunction "1_1") (pintype "passive"))
      (node (ref "U1") (pin "96") (pinfunction "PC6/TIM3_CH1/TIM8_CH1/U6_TX/SDIO_D6/DCMI_D0/I2S2_MCK_96") (pintype "passive"))
    )
    (net (code "85") (name "/PC7_U6_RX") (class "Default")
      (node (ref "P1") (pin "8") (pinfunction "8_8") (pintype "passive"))
      (node (ref "U1") (pin "97") (pinfunction "PC7/TIM3_CH2/TIM8_CH2/U6_RX/SDIO_D7/DCMI_D1/I2S3_MCK_97") (pintype "passive"))
    )
    (net (code "86") (name "/PC8_SDIO_0") (class "Default")
      (node (ref "U1") (pin "98") (pinfunction "PC8/TIM3_CH3/TIM8_CH3/U6_CK/SDIO_D0/DCMI_D2_98") (pintype "passive"))
    )
    (net (code "87") (name "/PC9_SDIO_1") (class "Default")
      (node (ref "U1") (pin "99") (pinfunction "PC9/TIM3_CH4/TIM8_CH4/I2C3_SDA/SDIO_D1/DCMI_D3/MCO2/I2S_CKIN_99") (pintype "passive"))
    )
    (net (code "88") (name "/PC10_SDIO_2") (class "Default")
      (node (ref "U1") (pin "111") (pinfunction "PC10/SPI3_SCK/U3_TX/U4_TX/SDIO_D2/DCMI_D8/I2S3_CK_111") (pintype "passive"))
    )
    (net (code "89") (name "/PC11_SDIO_3") (class "Default")
      (node (ref "U1") (pin "112") (pinfunction "PC11/SPI3_MISO/U3_RX/U4_RX/SDIO_D3/DCMI_D4/I2S3ext_SD_112") (pintype "passive"))
    )
    (net (code "90") (name "/PC12_SDIO_CK") (class "Default")
      (node (ref "U1") (pin "113") (pinfunction "PC12/SPI3_MOSI/U3_CK/U5_TX/SDIO_CK/DCMI_D9/I2S3_SD_113") (pintype "passive"))
    )
    (net (code "91") (name "/PD2_SDIO_CMD") (class "Default")
      (node (ref "U1") (pin "116") (pinfunction "PD2/TIM3_ETR/U5_RX/SDIO_CMD/DCMI_D11_116") (pintype "passive"))
    )
    (net (code "92") (name "/PD5_U2_TX") (class "Default")
      (node (ref "U1") (pin "119") (pinfunction "PD5/FSMC_NWE/U2_TX_119") (pintype "passive"))
      (node (ref "U7") (pin "11") (pinfunction "DIN1_11") (pintype "passive"))
    )
    (net (code "93") (name "/PD6_U2_RX") (class "Default")
      (node (ref "U1") (pin "122") (pinfunction "PD6/FSMC_NWAIT/U2_RX_122") (pintype "passive"))
      (node (ref "U7") (pin "12") (pinfunction "ROUT1_12") (pintype "passive"))
    )
    (net (code "94") (name "/POWER_ADC") (class "Default")
      (node (ref "U1") (pin "27") (pinfunction "PC1/ETH_MDC/ADC123_IN11_27") (pintype "passive"))
      (node (ref "U11") (pin "1") (pinfunction "OUTA_1") (pintype "output"))
      (node (ref "U11") (pin "2") (pinfunction "INA-_2") (pintype "input"))
    )
    (net (code "95") (name "/PWM1") (class "Default")
      (node (ref "P7") (pin "30") (pinfunction "30_30") (pintype "passive"))
      (node (ref "U1") (pin "81") (pinfunction "PD12/FSMC_A17/FSMC_ALE/TIM4_CH1/U3_RTS_81") (pintype "passive"))
    )
    (net (code "96") (name "/PWM2") (class "Default")
      (node (ref "P7") (pin "29") (pinfunction "29_29") (pintype "passive"))
      (node (ref "U1") (pin "82") (pinfunction "PD13/FSMC_A18/TIM4_CH2_82") (pintype "passive"))
    )
    (net (code "97") (name "/PWM3") (class "Default")
      (node (ref "P7") (pin "28") (pinfunction "28_28") (pintype "passive"))
      (node (ref "U1") (pin "85") (pinfunction "PD14/FSMC_D0/TIM4_CH3_85") (pintype "passive"))
    )
    (net (code "98") (name "/PWM4") (class "Default")
      (node (ref "P7") (pin "27") (pinfunction "27_27") (pintype "passive"))
      (node (ref "U1") (pin "86") (pinfunction "PD15/FSMC_D1/TIM4_CH4_86") (pintype "passive"))
    )
    (net (code "99") (name "/QYG_KC1") (class "Default")
      (node (ref "P6") (pin "36") (pinfunction "36_36") (pintype "passive"))
      (node (ref "U1") (pin "69") (pinfunction "PB10/SPI2_SCK/TIM2_CH3/U3_TX/I2C2_SCL/OTG_HS_ULPI_D3/I2S2_CK_69") (pintype "passive"))
    )
    (net (code "100") (name "/RDY") (class "Default")
      (node (ref "D11") (pin "K") (pinfunction "K_K") (pintype "passive"))
      (node (ref "R26") (pin "2") (pinfunction "2_2") (pintype "passive"))
      (node (ref "U6") (pin "40") (pinfunction "RDY_40") (pintype "passive"))
    )
    (net (code "101") (name "/RESET") (class "Default")
      (node (ref "C1") (pin "1") (pintype "passive"))
      (node (ref "R4") (pin "1") (pintype "passive"))
      (node (ref "RESET1") (pin "1") (pinfunction "1_1") (pintype "passive"))
      (node (ref "U1") (pin "25") (pinfunction "NRST_25") (pintype "passive"))
    )
    (net (code "102") (name "/RESET_YY") (class "Default")
      (node (ref "C82") (pin "1") (pinfunction "1_1") (pintype "passive"))
      (node (ref "R27") (pin "2") (pinfunction "2_2") (pintype "passive"))
      (node (ref "U6") (pin "28") (pinfunction "RESET_28") (pintype "passive"))
    )
    (net (code "103") (name "/RS485_1A") (class "Default")
      (node (ref "P7") (pin "7") (pinfunction "7_7") (pintype "passive"))
      (node (ref "R32") (pin "2") (pintype "passive"))
      (node (ref "R33") (pin "1") (pintype "passive"))
      (node (ref "U10") (pin "6") (pinfunction "A_6") (pintype "bidirectional"))
    )
    (net (code "104") (name "/RS485_1B") (class "Default")
      (node (ref "P7") (pin "8") (pinfunction "8_8") (pintype "passive"))
      (node (ref "R33") (pin "2") (pintype "passive"))
      (node (ref "R34") (pin "1") (pintype "passive"))
      (node (ref "U10") (pin "7") (pinfunction "~{B}_7") (pintype "bidirectional"))
    )
    (net (code "105") (name "/SPI2_MISO") (class "Default")
      (node (ref "U1") (pin "75") (pinfunction "PB14/SPI2_MISO/TIM1_CH2N/TIM8_CH2N/TIM12_CH1/U3_RTS/OTG_HS_DM/I2S2ext_SD_75") (pintype "passive"))
      (node (ref "U9") (pin "2") (pinfunction "DO_2") (pintype "passive"))
    )
    (net (code "106") (name "/SPI2_MOSI") (class "Default")
      (node (ref "U1") (pin "76") (pinfunction "PB15/SPI2_MOSI/TIM1_CH3N/TIM8_CH3N/TIM12_CH2/OTG_HS_DP/I2S2_SD_76") (pintype "passive"))
      (node (ref "U9") (pin "5") (pinfunction "DI_5") (pintype "passive"))
    )
    (net (code "107") (name "/SPI2_SCK") (class "Default")
      (node (ref "U1") (pin "74") (pinfunction "PB13/SPI2_SCK/TIM1_CH1N/U3_CTS/CAN2_TX/OTG_HS_ULPI_D6/OTG_HS_VBUS/ETH_MII_TXD1/ETH_RMII_TXD1/I2S2_CK_74") (pintype "passive"))
      (node (ref "U9") (pin "6") (pinfunction "CLK_6") (pintype "passive"))
    )
    (net (code "108") (name "/SPI_CLK") (class "Default")
      (node (ref "U6") (pin "42") (pinfunction "SPI_CLK_42") (pintype "passive"))
    )
    (net (code "109") (name "/SPI_CS") (class "Default")
      (node (ref "U6") (pin "43") (pinfunction "SPI_SSEL_43") (pintype "passive"))
    )
    (net (code "110") (name "/SPI_MISO") (class "Default")
      (node (ref "U6") (pin "45") (pinfunction "SPI_SO_45") (pintype "passive"))
    )
    (net (code "111") (name "/SPI_MOSI") (class "Default")
      (node (ref "U6") (pin "44") (pinfunction "SPI_SI_44") (pintype "passive"))
    )
    (net (code "112") (name "/SSD_KC1") (class "Default")
      (node (ref "P7") (pin "24") (pinfunction "24_24") (pintype "passive"))
      (node (ref "U1") (pin "100") (pinfunction "PA8/TIM1_CH1/U1_CK/I2C3_SCL/MCO1/OTG_FS_SOF_100") (pintype "passive"))
    )
    (net (code "113") (name "/SSD_KC2") (class "Default")
      (node (ref "P7") (pin "23") (pinfunction "23_23") (pintype "passive"))
      (node (ref "U1") (pin "110") (pinfunction "PA15/JTDI/SPI1_NSS/SPI3_NSS/TIM2_CH1_ETR/I2S3_WS_110") (pintype "passive"))
    )
    (net (code "114") (name "/SSD_KC3") (class "Default")
      (node (ref "P7") (pin "22") (pinfunction "22_22") (pintype "passive"))
      (node (ref "U1") (pin "114") (pinfunction "PD0/FSMC_D2/CAN1_RX_114") (pintype "passive"))
    )
    (net (code "115") (name "/SpeekL+") (class "Default")
      (node (ref "C81") (pin "2") (pinfunction "2_2") (pintype "passive"))
      (node (ref "FB5") (pin "2") (pinfunction "2_2") (pintype "passive"))
    )
    (net (code "116") (name "/SpeekL-") (class "Default")
      (node (ref "C80") (pin "2") (pinfunction "2_2") (pintype "passive"))
      (node (ref "FB4") (pin "1") (pinfunction "1_1") (pintype "passive"))
    )
    (net (code "117") (name "/SpeekR+") (class "Default")
      (node (ref "C17") (pin "2") (pinfunction "2_2") (pintype "passive"))
      (node (ref "FB2") (pin "2") (pinfunction "2_2") (pintype "passive"))
      (node (ref "P7") (pin "6") (pinfunction "6_6") (pintype "passive"))
    )
    (net (code "118") (name "/SpeekR-") (class "Default")
      (node (ref "C16") (pin "2") (pinfunction "2_2") (pintype "passive"))
      (node (ref "FB1") (pin "1") (pinfunction "1_1") (pintype "passive"))
      (node (ref "P7") (pin "5") (pinfunction "5_5") (pintype "passive"))
    )
    (net (code "119") (name "/TXX_KC1") (class "Default")
      (node (ref "P6") (pin "21") (pinfunction "21_21") (pintype "passive"))
      (node (ref "U1") (pin "44") (pinfunction "PC4/ETH_MII_RXD0/ETH_RMII_RXD0/ADC12_IN14_44") (pintype "passive"))
    )
    (net (code "120") (name "/TXX_KC2") (class "Default")
      (node (ref "P6") (pin "22") (pinfunction "22_22") (pintype "passive"))
      (node (ref "U1") (pin "45") (pinfunction "PC5/ETH_MII_RXD1/ETH_RMII_RXD1/ADC12_IN15_45") (pintype "passive"))
    )
    (net (code "121") (name "/TXX_KC3") (class "Default")
      (node (ref "P6") (pin "23") (pinfunction "23_23") (pintype "passive"))
      (node (ref "U1") (pin "46") (pinfunction "PB0/TIM1_CH2N/TIM3_CH3/TIM8_CH2N/OTG_HS_ULPI_D1/ETH_MII_RXD2/ADC12_IN8_46") (pintype "passive"))
    )
    (net (code "122") (name "/U2_RX") (class "Default")
      (node (ref "P7") (pin "3") (pinfunction "3_3") (pintype "passive"))
      (node (ref "U7") (pin "13") (pinfunction "RIN1_13") (pintype "passive"))
    )
    (net (code "123") (name "/U2_TX") (class "Default")
      (node (ref "P7") (pin "4") (pinfunction "4_4") (pintype "passive"))
      (node (ref "U7") (pin "14") (pinfunction "DOUT1_14") (pintype "passive"))
    )
    (net (code "124") (name "/U3_RX") (class "Default")
      (node (ref "P3") (pin "4") (pinfunction "4_4") (pintype "passive"))
      (node (ref "U1") (pin "78") (pinfunction "PD9/FSMC_D14/U3_RX_78") (pintype "passive"))
    )
    (net (code "125") (name "/U3_TX") (class "Default")
      (node (ref "P3") (pin "5") (pinfunction "5_5") (pintype "passive"))
      (node (ref "U1") (pin "77") (pinfunction "PD8/FSMC_D13/U3_TX_77") (pintype "passive"))
    )
    (net (code "126") (name "/VBAT") (class "Default")
      (node (ref "U1") (pin "6") (pinfunction "VBAT_6") (pintype "passive"))
    )
    (net (code "127") (name "/VCC_T") (class "Default")
      (node (ref "K1") (pin "2") (pinfunction "TAP1_2") (pintype "passive"))
      (node (ref "P7") (pin "31") (pinfunction "31_31") (pintype "passive"))
      (node (ref "U3") (pin "3") (pinfunction "Vin_3") (pintype "passive"))
      (node (ref "U8") (pin "3") (pinfunction "Vin_3") (pintype "passive"))
    )
    (net (code "128") (name "3.3V") (class "Default")
      (node (ref "C6") (pin "1") (pinfunction "VCC_1") (pintype "passive"))
      (node (ref "C7") (pin "2") (pintype "passive"))
      (node (ref "P1") (pin "5") (pinfunction "5_5") (pintype "passive"))
      (node (ref "P1") (pin "7") (pinfunction "7_7") (pintype "passive"))
      (node (ref "P3") (pin "2") (pinfunction "2_2") (pintype "passive"))
      (node (ref "R13") (pin "1") (pintype "passive"))
      (node (ref "U3") (pin "2") (pinfunction "Vout_2") (pintype "passive"))
    )
    (net (code "129") (name "AVCC_12") (class "Default")
      (node (ref "C12") (pin "1") (pinfunction "1_1") (pintype "passive"))
      (node (ref "C15") (pin "1") (pinfunction "1_1") (pintype "passive"))
      (node (ref "C35") (pin "1") (pinfunction "1_1") (pintype "passive"))
      (node (ref "C45") (pin "1") (pinfunction "1_1") (pintype "passive"))
      (node (ref "C46") (pin "1") (pinfunction "1_1") (pintype "passive"))
      (node (ref "C47") (pin "1") (pinfunction "1_1") (pintype "passive"))
      (node (ref "C72") (pin "1") (pinfunction "1_1") (pintype "passive"))
      (node (ref "C73") (pin "1") (pinfunction "1_1") (pintype "passive"))
      (node (ref "C74") (pin "1") (pinfunction "1_1") (pintype "passive"))
      (node (ref "C75") (pin "1") (pinfunction "1_1") (pintype "passive"))
      (node (ref "D10") (pin "2") (pinfunction "K_2") (pintype "passive"))
      (node (ref "D9") (pin "2") (pinfunction "K_2") (pintype "passive"))
      (node (ref "U12") (pin "12") (pinfunction "PVCCL_12") (pintype "passive"))
      (node (ref "U12") (pin "19") (pinfunction "PVCCL_19") (pintype "passive"))
      (node (ref "U12") (pin "26") (pinfunction "AVCC_26") (pintype "passive"))
      (node (ref "U12") (pin "29") (pinfunction "~{SD}_29") (pintype "passive"))
      (node (ref "U12") (pin "32") (pinfunction "PVCCR_32") (pintype "passive"))
      (node (ref "U12") (pin "39") (pinfunction "PVCCR_39") (pintype "passive"))
    )
    (net (code "130") (name "GND") (class "Default")
      (node (ref "C1") (pin "2") (pintype "passive"))
      (node (ref "C10") (pin "1") (pintype "passive"))
      (node (ref "C12") (pin "2") (pinfunction "2_2") (pintype "passive"))
      (node (ref "C13") (pin "2") (pintype "passive"))
      (node (ref "C14") (pin "2") (pintype "passive"))
      (node (ref "C15") (pin "2") (pinfunction "2_2") (pintype "passive"))
      (node (ref "C16") (pin "1") (pinfunction "1_1") (pintype "passive"))
      (node (ref "C17") (pin "1") (pinfunction "1_1") (pintype "passive"))
      (node (ref "C19") (pin "1") (pintype "passive"))
      (node (ref "C2") (pin "2") (pintype "passive"))
      (node (ref "C20") (pin "1") (pintype "passive"))
      (node (ref "C21") (pin "1") (pintype "passive"))
      (node (ref "C22") (pin "1") (pintype "passive"))
      (node (ref "C23") (pin "1") (pintype "passive"))
      (node (ref "C24") (pin "1") (pintype "passive"))
      (node (ref "C25") (pin "1") (pintype "passive"))
      (node (ref "C26") (pin "1") (pintype "passive"))
      (node (ref "C27") (pin "1") (pintype "passive"))
      (node (ref "C28") (pin "1") (pintype "passive"))
      (node (ref "C29") (pin "1") (pintype "passive"))
      (node (ref "C3") (pin "2") (pintype "passive"))
      (node (ref "C30") (pin "1") (pintype "passive"))
      (node (ref "C32") (pin "2") (pinfunction "2_2") (pintype "passive"))
      (node (ref "C33") (pin "2") (pinfunction "2_2") (pintype "passive"))
      (node (ref "C34") (pin "2") (pinfunction "2_2") (pintype "passive"))
      (node (ref "C35") (pin "2") (pinfunction "2_2") (pintype "passive"))
      (node (ref "C36") (pin "1") (pintype "passive"))
      (node (ref "C38") (pin "2") (pinfunction "GND_2") (pintype "passive"))
      (node (ref "C4") (pin "1") (pintype "passive"))
      (node (ref "C40") (pin "1") (pintype "passive"))
      (node (ref "C42") (pin "2") (pinfunction "2_2") (pintype "passive"))
      (node (ref "C43") (pin "2") (pintype "passive"))
      (node (ref "C44") (pin "2") (pintype "passive"))
      (node (ref "C45") (pin "2") (pinfunction "2_2") (pintype "passive"))
      (node (ref "C46") (pin "2") (pinfunction "2_2") (pintype "passive"))
      (node (ref "C47") (pin "2") (pinfunction "2_2") (pintype "passive"))
      (node (ref "C48") (pin "1") (pinfunction "1_1") (pintype "passive"))
      (node (ref "C49") (pin "2") (pinfunction "2_2") (pintype "passive"))
      (node (ref "C50") (pin "2") (pinfunction "2_2") (pintype "passive"))
      (node (ref "C52") (pin "2") (pinfunction "2_2") (pintype "passive"))
      (node (ref "C53") (pin "1") (pinfunction "1_1") (pintype "passive"))
      (node (ref "C54") (pin "2") (pinfunction "2_2") (pintype "passive"))
      (node (ref "C55") (pin "2") (pinfunction "2_2") (pintype "passive"))
      (node (ref "C56") (pin "1") (pinfunction "1_1") (pintype "passive"))
      (node (ref "C57") (pin "2") (pinfunction "2_2") (pintype "passive"))
      (node (ref "C58") (pin "2") (pinfunction "2_2") (pintype "passive"))
      (node (ref "C59") (pin "2") (pinfunction "2_2") (pintype "passive"))
      (node (ref "C6") (pin "2") (pinfunction "GND_2") (pintype "passive"))
      (node (ref "C60") (pin "1") (pinfunction "1_1") (pintype "passive"))
      (node (ref "C61") (pin "2") (pinfunction "2_2") (pintype "passive"))
      (node (ref "C62") (pin "1") (pinfunction "1_1") (pintype "passive"))
      (node (ref "C63") (pin "2") (pinfunction "2_2") (pintype "passive"))
      (node (ref "C66") (pin "2") (pinfunction "2_2") (pintype "passive"))
      (node (ref "C67") (pin "1") (pinfunction "1_1") (pintype "passive"))
      (node (ref "C68") (pin "2") (pinfunction "2_2") (pintype "passive"))
      (node (ref "C69") (pin "2") (pinfunction "2_2") (pintype "passive"))
      (node (ref "C7") (pin "1") (pintype "passive"))
      (node (ref "C70") (pin "2") (pinfunction "2_2") (pintype "passive"))
      (node (ref "C71") (pin "2") (pinfunction "2_2") (pintype "passive"))
      (node (ref "C72") (pin "2") (pinfunction "2_2") (pintype "passive"))
      (node (ref "C73") (pin "2") (pinfunction "2_2") (pintype "passive"))
      (node (ref "C74") (pin "2") (pinfunction "2_2") (pintype "passive"))
      (node (ref "C75") (pin "2") (pinfunction "2_2") (pintype "passive"))
      (node (ref "C76") (pin "1") (pinfunction "1_1") (pintype "passive"))
      (node (ref "C79") (pin "1") (pinfunction "1_1") (pintype "passive"))
      (node (ref "C8") (pin "2") (pinfunction "2_2") (pintype "passive"))
      (node (ref "C80") (pin "1") (pinfunction "1_1") (pintype "passive"))
      (node (ref "C81") (pin "1") (pinfunction "1_1") (pintype "passive"))
      (node (ref "C82") (pin "2") (pinfunction "2_2") (pintype "passive"))
      (node (ref "C9") (pin "1") (pinfunction "1_1") (pintype "passive"))
      (node (ref "D12") (pin "K") (pinfunction "K_K") (pintype "passive"))
      (node (ref "D6") (pin "1") (pinfunction "A_1") (pintype "passive"))
      (node (ref "D7") (pin "1") (pinfunction "A_1") (pintype "passive"))
      (node (ref "D8") (pin "K") (pinfunction "K_K") (pintype "passive"))
      (node (ref "J3") (pin "1") (pinfunction "-VIN_1") (pintype "passive"))
      (node (ref "J3") (pin "5") (pinfunction "GND_5") (pintype "passive"))
      (node (ref "P1") (pin "4") (pinfunction "4_4") (pintype "passive"))
      (node (ref "P2") (pin "2") (pinfunction "2_2") (pintype "passive"))
      (node (ref "P3") (pin "1") (pinfunction "1_1") (pintype "passive"))
      (node (ref "P3") (pin "6") (pinfunction "6_6") (pintype "passive"))
      (node (ref "P3") (pin "7") (pinfunction "7_7") (pintype "passive"))
      (node (ref "P7") (pin "2") (pinfunction "2_2") (pintype "passive"))
      (node (ref "Q4") (pin "2") (pinfunction "E_2") (pintype "passive"))
      (node (ref "R1") (pin "2") (pintype "passive"))
      (node (ref "R10") (pin "1") (pinfunction "1_1") (pintype "passive"))
      (node (ref "R15") (pin "2") (pintype "passive"))
      (node (ref "R18") (pin "1") (pinfunction "1_1") (pintype "passive"))
      (node (ref "R19") (pin "1") (pinfunction "1_1") (pintype "passive"))
      (node (ref "R2") (pin "1") (pintype "passive"))
      (node (ref "R21") (pin "2") (pinfunction "2_2") (pintype "passive"))
      (node (ref "R24") (pin "1") (pinfunction "1_1") (pintype "passive"))
      (node (ref "R34") (pin "2") (pintype "passive"))
      (node (ref "R36") (pin "1") (pinfunction "1_1") (pintype "passive"))
      (node (ref "R41") (pin "1") (pintype "passive"))
      (node (ref "R6") (pin "2") (pintype "passive"))
      (node (ref "R7") (pin "2") (pintype "passive"))
      (node (ref "R8") (pin "2") (pintype "passive"))
      (node (ref "RESET1") (pin "2") (pinfunction "2_2") (pintype "passive"))
      (node (ref "U1") (pin "107") (pinfunction "VSS_107") (pintype "passive"))
      (node (ref "U1") (pin "120") (pinfunction "VSS_120") (pintype "passive"))
      (node (ref "U1") (pin "130") (pinfunction "VSS_130") (pintype "passive"))
      (node (ref "U1") (pin "16") (pinfunction "VSS_16") (pintype "passive"))
      (node (ref "U1") (pin "31") (pinfunction "VSSA_31") (pintype "passive"))
      (node (ref "U1") (pin "38") (pinfunction "VSS_38") (pintype "passive"))
      (node (ref "U1") (pin "51") (pinfunction "VSS_51") (pintype "passive"))
      (node (ref "U1") (pin "61") (pinfunction "VSS_61") (pintype "passive"))
      (node (ref "U1") (pin "83") (pinfunction "VSS_83") (pintype "passive"))
      (node (ref "U1") (pin "94") (pinfunction "VSS_94") (pintype "passive"))
      (node (ref "U10") (pin "5") (pinfunction "GND_5") (pintype "power_in"))
      (node (ref "U11") (pin "11") (pinfunction "V-_11") (pintype "power_in"))
      (node (ref "U12") (pin "11") (pinfunction "PGNDL_11") (pintype "passive"))
      (node (ref "U12") (pin "20") (pinfunction "PGNDL_20") (pintype "passive"))
      (node (ref "U12") (pin "24") (pinfunction "AGND_24") (pintype "passive"))
      (node (ref "U12") (pin "25") (pinfunction "MUTE_25") (pintype "passive"))
      (node (ref "U12") (pin "28") (pinfunction "AGND_28") (pintype "passive"))
      (node (ref "U12") (pin "31") (pinfunction "PGNDR_31") (pintype "passive"))
      (node (ref "U12") (pin "40") (pinfunction "PGNDR_40") (pintype "passive"))
      (node (ref "U12") (pin "6") (pinfunction "REFGND_6") (pintype "passive"))
      (node (ref "U12") (pin "7") (pinfunction "AGND1_7") (pintype "passive"))
      (node (ref "U12") (pin "8") (pinfunction "~{FADE}_8") (pintype "passive"))
      (node (ref "U2") (pin "2") (pinfunction "GND_2") (pintype "passive"))
      (node (ref "U2") (pin "8") (pinfunction "RS_8") (pintype "passive"))
      (node (ref "U3") (pin "1") (pinfunction "GND_1") (pintype "passive"))
      (node (ref "U4") (pin "2") (pinfunction "GND_2") (pintype "passive"))
      (node (ref "U4") (pin "8") (pinfunction "RS_8") (pintype "passive"))
      (node (ref "U5") (pin "5") (pinfunction "GND_5") (pintype "passive"))
      (node (ref "U6") (pin "10") (pinfunction "AGND_10") (pintype "passive"))
      (node (ref "U6") (pin "14") (pinfunction "AGND_14") (pintype "passive"))
      (node (ref "U6") (pin "25") (pinfunction "GND_25") (pintype "passive"))
      (node (ref "U6") (pin "37") (pinfunction "GND_37") (pintype "passive"))
      (node (ref "U6") (pin "4") (pinfunction "GND_4") (pintype "passive"))
      (node (ref "U6") (pin "52") (pinfunction "GND_52") (pintype "passive"))
      (node (ref "U6") (pin "64") (pinfunction "GND_64") (pintype "passive"))
      (node (ref "U7") (pin "15") (pinfunction "GND_15") (pintype "passive"))
      (node (ref "U8") (pin "1") (pinfunction "GND_1") (pintype "passive"))
      (node (ref "U9") (pin "4") (pinfunction "GND_4") (pintype "passive"))
    )
    (net (code "131") (name "Net-(BEEP1-G)") (class "Default")
      (node (ref "BEEP1") (pin "2") (pinfunction "G_2") (pintype "passive"))
      (node (ref "Q4") (pin "3") (pinfunction "C_3") (pintype "passive"))
    )
    (net (code "132") (name "Net-(C11-Pad1)") (class "Default")
      (node (ref "C11") (pin "1") (pinfunction "1_1") (pintype "passive"))
      (node (ref "R15") (pin "1") (pintype "passive"))
    )
    (net (code "133") (name "Net-(C18-Pad1)") (class "Default")
      (node (ref "C18") (pin "1") (pinfunction "1_1") (pintype "passive"))
      (node (ref "FB1") (pin "2") (pinfunction "2_2") (pintype "passive"))
      (node (ref "U12") (pin "37") (pinfunction "ROUTN_37") (pintype "passive"))
      (node (ref "U12") (pin "38") (pinfunction "ROUTN_38") (pintype "passive"))
    )
    (net (code "134") (name "Net-(C31-Pad2)") (class "Default")
      (node (ref "C31") (pin "2") (pinfunction "2_2") (pintype "passive"))
      (node (ref "FB2") (pin "1") (pinfunction "1_1") (pintype "passive"))
      (node (ref "U12") (pin "33") (pinfunction "ROUTP_33") (pintype "passive"))
      (node (ref "U12") (pin "34") (pinfunction "ROUTP_34") (pintype "passive"))
    )
    (net (code "135") (name "Net-(C77-Pad2)") (class "Default")
      (node (ref "C77") (pin "2") (pinfunction "2_2") (pintype "passive"))
      (node (ref "FB4") (pin "2") (pinfunction "2_2") (pintype "passive"))
      (node (ref "U12") (pin "13") (pinfunction "LOUTN_13") (pintype "passive"))
      (node (ref "U12") (pin "14") (pinfunction "LOUTN_14") (pintype "passive"))
    )
    (net (code "136") (name "Net-(C78-Pad2)") (class "Default")
      (node (ref "C78") (pin "2") (pinfunction "2_2") (pintype "passive"))
      (node (ref "FB5") (pin "1") (pinfunction "1_1") (pintype "passive"))
      (node (ref "U12") (pin "17") (pinfunction "LOUTP_17") (pintype "passive"))
      (node (ref "U12") (pin "18") (pinfunction "LOUTP_18") (pintype "passive"))
    )
    (net (code "137") (name "Net-(D1-PadA)") (class "Default")
      (node (ref "D1") (pin "A") (pinfunction "A_A") (pintype "passive"))
      (node (ref "PR1") (pin "1") (pinfunction "1_1") (pintype "passive"))
    )
    (net (code "138") (name "Net-(D2-PadA)") (class "Default")
      (node (ref "D2") (pin "A") (pinfunction "A_A") (pintype "passive"))
      (node (ref "PR1") (pin "2") (pinfunction "2_2") (pintype "passive"))
    )
    (net (code "139") (name "Net-(D3-PadA)") (class "Default")
      (node (ref "D3") (pin "A") (pinfunction "A_A") (pintype "passive"))
      (node (ref "R13") (pin "2") (pintype "passive"))
    )
    (net (code "140") (name "Net-(D4-PadA)") (class "Default")
      (node (ref "D4") (pin "A") (pinfunction "A_A") (pintype "passive"))
      (node (ref "PR1") (pin "3") (pinfunction "3_3") (pintype "passive"))
    )
    (net (code "141") (name "Net-(D5-PadA)") (class "Default")
      (node (ref "D5") (pin "A") (pinfunction "A_A") (pintype "passive"))
      (node (ref "PR1") (pin "4") (pinfunction "4_4") (pintype "passive"))
    )
    (net (code "142") (name "Net-(D7-K)") (class "Default")
      (node (ref "C5") (pin "1") (pinfunction "1_1") (pintype "passive"))
      (node (ref "D7") (pin "2") (pinfunction "K_2") (pintype "passive"))
      (node (ref "L1") (pin "1") (pinfunction "1_1") (pintype "passive"))
      (node (ref "U5") (pin "1") (pinfunction "SW_1") (pintype "passive"))
    )
    (net (code "143") (name "Net-(D8-PadA)") (class "Default")
      (node (ref "D8") (pin "A") (pinfunction "A_A") (pintype "passive"))
      (node (ref "R25") (pin "2") (pintype "passive"))
    )
    (net (code "144") (name "Net-(D11-PadA)") (class "Default")
      (node (ref "D11") (pin "A") (pinfunction "A_A") (pintype "passive"))
      (node (ref "R28") (pin "2") (pinfunction "2_2") (pintype "passive"))
    )
    (net (code "145") (name "Net-(D12-PadA)") (class "Default")
      (node (ref "D12") (pin "A") (pinfunction "A_A") (pintype "passive"))
      (node (ref "R29") (pin "2") (pintype "passive"))
    )
    (net (code "146") (name "Net-(Q4-B)") (class "Default")
      (node (ref "Q4") (pin "1") (pinfunction "B_1") (pintype "passive"))
      (node (ref "R40") (pin "2") (pintype "passive"))
      (node (ref "R41") (pin "2") (pintype "passive"))
    )
    (net (code "147") (name "Net-(U1-PDR_ON)") (class "Default")
      (node (ref "R20") (pin "1") (pintype "passive"))
      (node (ref "U1") (pin "143") (pinfunction "PDR_ON_143") (pintype "passive"))
    )
    (net (code "148") (name "Net-(U1-PH0-OSC_IN)") (class "Default")
      (node (ref "C4") (pin "2") (pintype "passive"))
      (node (ref "R12") (pin "2") (pintype "passive"))
      (node (ref "U1") (pin "23") (pinfunction "PH0-OSC_IN_23") (pintype "passive"))
      (node (ref "Y2") (pin "2") (pinfunction "OSC2_2") (pintype "passive"))
    )
    (net (code "149") (name "Net-(U1-PH1-OSC_OUT)") (class "Default")
      (node (ref "C10") (pin "2") (pintype "passive"))
      (node (ref "R12") (pin "1") (pintype "passive"))
      (node (ref "U1") (pin "24") (pinfunction "PH1-OSC_OUT_24") (pintype "passive"))
      (node (ref "Y2") (pin "1") (pinfunction "OSC1_1") (pintype "passive"))
    )
    (net (code "150") (name "Net-(U1-Vcap_1)") (class "Default")
      (node (ref "C13") (pin "1") (pintype "passive"))
      (node (ref "U1") (pin "71") (pinfunction "Vcap_1_71") (pintype "passive"))
    )
    (net (code "151") (name "Net-(U1-Vcap_2)") (class "Default")
      (node (ref "C14") (pin "1") (pintype "passive"))
      (node (ref "U1") (pin "106") (pinfunction "Vcap_2_106") (pintype "passive"))
    )
    (net (code "152") (name "Net-(U5-BST)") (class "Default")
      (node (ref "C5") (pin "2") (pinfunction "2_2") (pintype "passive"))
      (node (ref "U5") (pin "8") (pinfunction "BST_8") (pintype "passive"))
    )
    (net (code "153") (name "Net-(U5-COMP)") (class "Default")
      (node (ref "C11") (pin "2") (pinfunction "2_2") (pintype "passive"))
      (node (ref "U5") (pin "3") (pinfunction "COMP_3") (pintype "passive"))
    )
    (net (code "154") (name "Net-(U5-EN)") (class "Default")
      (node (ref "R3") (pin "2") (pintype "passive"))
      (node (ref "R7") (pin "1") (pintype "passive"))
      (node (ref "U5") (pin "2") (pinfunction "EN_2") (pintype "passive"))
    )
    (net (code "155") (name "Net-(U5-FB)") (class "Default")
      (node (ref "R5") (pin "1") (pintype "passive"))
      (node (ref "R6") (pin "1") (pintype "passive"))
      (node (ref "U5") (pin "4") (pinfunction "FB_4") (pintype "passive"))
    )
    (net (code "156") (name "Net-(U5-FREQ)") (class "Default")
      (node (ref "R8") (pin "1") (pintype "passive"))
      (node (ref "U5") (pin "6") (pinfunction "FREQ_6") (pintype "passive"))
    )
    (net (code "157") (name "Net-(U6-A1)") (class "Default")
      (node (ref "U6") (pin "53") (pinfunction "A1_53") (pintype "passive"))
      (node (ref "U6") (pin "54") (pinfunction "A2_54") (pintype "passive"))
    )
    (net (code "158") (name "Net-(U6-A3)") (class "Default")
      (node (ref "R24") (pin "2") (pinfunction "2_2") (pintype "passive"))
      (node (ref "U6") (pin "62") (pinfunction "A3_62") (pintype "passive"))
    )
    (net (code "159") (name "Net-(U6-A4)") (class "Default")
      (node (ref "R23") (pin "1") (pinfunction "1_1") (pintype "passive"))
      (node (ref "U6") (pin "29") (pinfunction "A4_29") (pintype "passive"))
    )
    (net (code "160") (name "Net-(U6-AO_N)") (class "Default")
      (node (ref "C67") (pin "2") (pinfunction "2_2") (pintype "passive"))
      (node (ref "U6") (pin "9") (pinfunction "AO_N_9") (pintype "passive"))
    )
    (net (code "161") (name "Net-(U6-AO_P)") (class "Default")
      (node (ref "C64") (pin "2") (pinfunction "2_2") (pintype "passive"))
      (node (ref "U6") (pin "8") (pinfunction "AO_P_8") (pintype "passive"))
    )
    (net (code "162") (name "Net-(U6-BAUD1)") (class "Default")
      (node (ref "R21") (pin "1") (pinfunction "1_1") (pintype "passive"))
      (node (ref "U6") (pin "56") (pinfunction "BAUD1_56") (pintype "passive"))
    )
    (net (code "163") (name "Net-(U6-BAUD2)") (class "Default")
      (node (ref "R22") (pin "1") (pinfunction "1_1") (pintype "passive"))
      (node (ref "U6") (pin "55") (pinfunction "BAUD2_55") (pintype "passive"))
    )
    (net (code "164") (name "Net-(U6-RREF)") (class "Default")
      (node (ref "R19") (pin "2") (pinfunction "2_2") (pintype "passive"))
      (node (ref "U6") (pin "3") (pinfunction "RREF_3") (pintype "passive"))
    )
    (net (code "165") (name "Net-(U6-VCM)") (class "Default")
      (node (ref "C69") (pin "1") (pinfunction "1_1") (pintype "passive"))
      (node (ref "U6") (pin "11") (pinfunction "VCM_11") (pintype "passive"))
    )
    (net (code "166") (name "Net-(U6-VREF)") (class "Default")
      (node (ref "C48") (pin "2") (pinfunction "2_2") (pintype "passive"))
      (node (ref "U6") (pin "18") (pinfunction "VREF_18") (pintype "passive"))
    )
    (net (code "167") (name "Net-(U6-XTALI)") (class "Default")
      (node (ref "C76") (pin "2") (pinfunction "2_2") (pintype "passive"))
      (node (ref "U6") (pin "26") (pinfunction "XTALI_26") (pintype "passive"))
      (node (ref "Y1") (pin "1") (pinfunction "1_1") (pintype "passive"))
    )
    (net (code "168") (name "Net-(U6-XTALO)") (class "Default")
      (node (ref "C79") (pin "2") (pinfunction "2_2") (pintype "passive"))
      (node (ref "U6") (pin "27") (pinfunction "XTALO_27") (pintype "passive"))
      (node (ref "Y1") (pin "2") (pinfunction "2_2") (pintype "passive"))
    )
    (net (code "169") (name "Net-(U7-C1+)") (class "Default")
      (node (ref "C37") (pin "1") (pinfunction "1_1") (pintype "passive"))
      (node (ref "U7") (pin "1") (pinfunction "C1+_1") (pintype "passive"))
    )
    (net (code "170") (name "Net-(U7-C1-)") (class "Default")
      (node (ref "C37") (pin "2") (pinfunction "2_2") (pintype "passive"))
      (node (ref "U7") (pin "3") (pinfunction "C1-_3") (pintype "passive"))
    )
    (net (code "171") (name "Net-(U7-C2+)") (class "Default")
      (node (ref "C41") (pin "1") (pinfunction "1_1") (pintype "passive"))
      (node (ref "U7") (pin "4") (pinfunction "C2+_4") (pintype "passive"))
    )
    (net (code "172") (name "Net-(U7-C2-)") (class "Default")
      (node (ref "C41") (pin "2") (pinfunction "2_2") (pintype "passive"))
      (node (ref "U7") (pin "5") (pinfunction "C2-_5") (pintype "passive"))
    )
    (net (code "173") (name "Net-(U7-V+)") (class "Default")
      (node (ref "C39") (pin "1") (pinfunction "1_1") (pintype "passive"))
      (node (ref "U7") (pin "2") (pinfunction "V+_2") (pintype "passive"))
    )
    (net (code "174") (name "Net-(U7-V-)") (class "Default")
      (node (ref "C42") (pin "1") (pinfunction "1_1") (pintype "passive"))
      (node (ref "U7") (pin "6") (pinfunction "V-_6") (pintype "passive"))
    )
    (net (code "175") (name "Net-(U11A-INA+)") (class "Default")
      (node (ref "R35") (pin "1") (pinfunction "1_1") (pintype "passive"))
      (node (ref "R36") (pin "2") (pinfunction "2_2") (pintype "passive"))
      (node (ref "U11") (pin "3") (pinfunction "INA+_3") (pintype "input"))
    )
    (net (code "176") (name "Net-(U12-AVDD)") (class "Default")
      (node (ref "C56") (pin "2") (pinfunction "2_2") (pintype "passive"))
      (node (ref "U12") (pin "3") (pinfunction "AVDD_3") (pintype "passive"))
      (node (ref "U12") (pin "4") (pinfunction "VREF_4") (pintype "passive"))
      (node (ref "U12") (pin "5") (pinfunction "VOLUME_5") (pintype "passive"))
    )
    (net (code "177") (name "Net-(U12-BSLN)") (class "Default")
      (node (ref "C77") (pin "1") (pinfunction "1_1") (pintype "passive"))
      (node (ref "U12") (pin "15") (pinfunction "BSLN_15") (pintype "passive"))
    )
    (net (code "178") (name "Net-(U12-BSLP)") (class "Default")
      (node (ref "C78") (pin "1") (pinfunction "1_1") (pintype "passive"))
      (node (ref "U12") (pin "16") (pinfunction "BSLP_16") (pintype "passive"))
    )
    (net (code "179") (name "Net-(U12-BSRN)") (class "Default")
      (node (ref "C18") (pin "2") (pinfunction "2_2") (pintype "passive"))
      (node (ref "U12") (pin "36") (pinfunction "BSRN_36") (pintype "passive"))
    )
    (net (code "180") (name "Net-(U12-BSRP)") (class "Default")
      (node (ref "C31") (pin "1") (pinfunction "1_1") (pintype "passive"))
      (node (ref "U12") (pin "35") (pinfunction "BSRP_35") (pintype "passive"))
    )
    (net (code "181") (name "Net-(U12-COSC)") (class "Default")
      (node (ref "C63") (pin "1") (pinfunction "1_1") (pintype "passive"))
      (node (ref "U12") (pin "22") (pinfunction "COSC_22") (pintype "passive"))
    )
    (net (code "182") (name "Net-(U12-LINN)") (class "Default")
      (node (ref "C65") (pin "2") (pinfunction "2_2") (pintype "passive"))
      (node (ref "U12") (pin "10") (pinfunction "LINN_10") (pintype "passive"))
    )
    (net (code "183") (name "Net-(U12-LINP)") (class "Default")
      (node (ref "C62") (pin "2") (pinfunction "2_2") (pintype "passive"))
      (node (ref "U12") (pin "9") (pinfunction "LINP_9") (pintype "passive"))
    )
    (net (code "184") (name "Net-(U12-RINN)") (class "Default")
      (node (ref "C51") (pin "2") (pinfunction "2_2") (pintype "passive"))
      (node (ref "U12") (pin "1") (pinfunction "RINN_1") (pintype "passive"))
    )
    (net (code "185") (name "Net-(U12-RINP)") (class "Default")
      (node (ref "C53") (pin "2") (pinfunction "2_2") (pintype "passive"))
      (node (ref "U12") (pin "2") (pinfunction "RINP_2") (pintype "passive"))
    )
    (net (code "186") (name "Net-(U12-ROSC)") (class "Default")
      (node (ref "R18") (pin "2") (pinfunction "2_2") (pintype "passive"))
      (node (ref "U12") (pin "23") (pinfunction "ROSC_23") (pintype "passive"))
    )
    (net (code "187") (name "Net-(U12-V2P5)") (class "Default")
      (node (ref "C57") (pin "1") (pinfunction "1_1") (pintype "passive"))
      (node (ref "U12") (pin "27") (pinfunction "V2P5_27") (pintype "passive"))
    )
    (net (code "188") (name "Net-(U12-VCLAMPL)") (class "Default")
      (node (ref "C66") (pin "1") (pinfunction "1_1") (pintype "passive"))
      (node (ref "U12") (pin "21") (pinfunction "VCLAMPL_21") (pintype "passive"))
    )
    (net (code "189") (name "Net-(U12-VCLAMPR)") (class "Default")
      (node (ref "C52") (pin "1") (pinfunction "1_1") (pintype "passive"))
      (node (ref "U12") (pin "30") (pinfunction "VCLAMPR_30") (pintype "passive"))
    )
    (net (code "190") (name "VCC") (class "Default")
      (node (ref "J3") (pin "3") (pinfunction "+V0_3") (pintype "passive"))
      (node (ref "K1") (pin "3") (pinfunction "I/O1_3") (pintype "passive"))
      (node (ref "U11") (pin "4") (pinfunction "V+_4") (pintype "power_in"))
    )
    (net (code "191") (name "VCC3.3") (class "Default")
      (node (ref "BEEP1") (pin "1") (pinfunction "P_1") (pintype "passive"))
      (node (ref "C19") (pin "2") (pintype "passive"))
      (node (ref "C2") (pin "1") (pintype "passive"))
      (node (ref "C20") (pin "2") (pintype "passive"))
      (node (ref "C21") (pin "2") (pintype "passive"))
      (node (ref "C22") (pin "2") (pintype "passive"))
      (node (ref "C23") (pin "2") (pintype "passive"))
      (node (ref "C24") (pin "2") (pintype "passive"))
      (node (ref "C25") (pin "2") (pintype "passive"))
      (node (ref "C26") (pin "2") (pintype "passive"))
      (node (ref "C27") (pin "2") (pintype "passive"))
      (node (ref "C28") (pin "2") (pintype "passive"))
      (node (ref "C29") (pin "2") (pintype "passive"))
      (node (ref "C3") (pin "1") (pintype "passive"))
      (node (ref "C30") (pin "2") (pintype "passive"))
      (node (ref "C36") (pin "2") (pintype "passive"))
      (node (ref "C38") (pin "1") (pinfunction "VCC_1") (pintype "passive"))
      (node (ref "C39") (pin "2") (pinfunction "2_2") (pintype "passive"))
      (node (ref "C40") (pin "2") (pintype "passive"))
      (node (ref "C43") (pin "1") (pintype "passive"))
      (node (ref "C44") (pin "1") (pintype "passive"))
      (node (ref "C70") (pin "1") (pinfunction "1_1") (pintype "passive"))
      (node (ref "C71") (pin "1") (pinfunction "1_1") (pintype "passive"))
      (node (ref "D6") (pin "2") (pinfunction "K_2") (pintype "passive"))
      (node (ref "P2") (pin "1") (pinfunction "1_1") (pintype "passive"))
      (node (ref "P7") (pin "32") (pinfunction "32_32") (pintype "passive"))
      (node (ref "PR1") (pin "5") (pinfunction "5_5") (pintype "passive"))
      (node (ref "PR1") (pin "6") (pinfunction "6_6") (pintype "passive"))
      (node (ref "PR1") (pin "7") (pinfunction "7_7") (pintype "passive"))
      (node (ref "PR1") (pin "8") (pinfunction "8_8") (pintype "passive"))
      (node (ref "R11") (pin "1") (pinfunction "1_1") (pintype "passive"))
      (node (ref "R20") (pin "2") (pintype "passive"))
      (node (ref "R25") (pin "1") (pintype "passive"))
      (node (ref "R28") (pin "1") (pinfunction "1_1") (pintype "passive"))
      (node (ref "R32") (pin "1") (pintype "passive"))
      (node (ref "R4") (pin "2") (pintype "passive"))
      (node (ref "U1") (pin "108") (pinfunction "VDD_108") (pintype "passive"))
      (node (ref "U1") (pin "121") (pinfunction "VDD_121") (pintype "passive"))
      (node (ref "U1") (pin "131") (pinfunction "VDD_131") (pintype "passive"))
      (node (ref "U1") (pin "144") (pinfunction "VDD_144") (pintype "passive"))
      (node (ref "U1") (pin "17") (pinfunction "VDD_17") (pintype "passive"))
      (node (ref "U1") (pin "30") (pinfunction "VDD_30") (pintype "passive"))
      (node (ref "U1") (pin "32") (pinfunction "Vref+_32") (pintype "passive"))
      (node (ref "U1") (pin "33") (pinfunction "VDDA_33") (pintype "passive"))
      (node (ref "U1") (pin "39") (pinfunction "VDD_39") (pintype "passive"))
      (node (ref "U1") (pin "52") (pinfunction "VDD_52") (pintype "passive"))
      (node (ref "U1") (pin "62") (pinfunction "VDD_62") (pintype "passive"))
      (node (ref "U1") (pin "72") (pinfunction "VDD_72") (pintype "passive"))
      (node (ref "U1") (pin "84") (pinfunction "VDD_84") (pintype "passive"))
      (node (ref "U1") (pin "95") (pinfunction "VDD_95") (pintype "passive"))
      (node (ref "U10") (pin "8") (pinfunction "VCC_8") (pintype "power_in"))
      (node (ref "U2") (pin "3") (pinfunction "VCC_3") (pintype "passive"))
      (node (ref "U4") (pin "3") (pinfunction "VCC_3") (pintype "passive"))
      (node (ref "U6") (pin "20") (pinfunction "PWR_IN_20") (pintype "passive"))
      (node (ref "U7") (pin "16") (pinfunction "VCC_16") (pintype "passive"))
      (node (ref "U8") (pin "2") (pinfunction "Vout_2") (pintype "passive"))
      (node (ref "U9") (pin "3") (pinfunction "~{WP}_3") (pintype "passive"))
      (node (ref "U9") (pin "7") (pinfunction "~{HOLD}_7") (pintype "passive"))
      (node (ref "U9") (pin "8") (pinfunction "VCC_8") (pintype "passive"))
    )
    (net (code "192") (name "VCC12") (class "Default")
      (node (ref "C9") (pin "2") (pinfunction "2_2") (pintype "passive"))
      (node (ref "D10") (pin "1") (pinfunction "A_1") (pintype "passive"))
      (node (ref "D9") (pin "1") (pinfunction "A_1") (pintype "passive"))
      (node (ref "L1") (pin "2") (pinfunction "2_2") (pintype "passive"))
      (node (ref "R29") (pin "1") (pintype "passive"))
      (node (ref "R5") (pin "2") (pintype "passive"))
    )
    (net (code "193") (name "VCC24") (class "Default")
      (node (ref "J3") (pin "2") (pinfunction "+VIN_2") (pintype "passive"))
      (node (ref "K1") (pin "5") (pinfunction "TAP2_5") (pintype "passive"))
      (node (ref "P7") (pin "1") (pinfunction "1_1") (pintype "passive"))
    )
    (net (code "194") (name "VCC24_T") (class "Default")
      (node (ref "C8") (pin "1") (pinfunction "1_1") (pintype "passive"))
      (node (ref "K1") (pin "6") (pinfunction "I/O2_6") (pintype "passive"))
      (node (ref "R3") (pin "1") (pintype "passive"))
      (node (ref "R35") (pin "2") (pinfunction "2_2") (pintype "passive"))
      (node (ref "U5") (pin "7") (pinfunction "VIN_7") (pintype "passive"))
    )
    (net (code "195") (name "VDD12") (class "Default")
      (node (ref "C34") (pin "1") (pinfunction "1_1") (pintype "passive"))
      (node (ref "C58") (pin "1") (pinfunction "1_1") (pintype "passive"))
      (node (ref "C59") (pin "1") (pinfunction "1_1") (pintype "passive"))
      (node (ref "U6") (pin "1") (pinfunction "VDD12_1") (pintype "passive"))
      (node (ref "U6") (pin "23") (pinfunction "VDD12_O_23") (pintype "passive"))
    )
    (net (code "196") (name "VDD33") (class "Default")
      (node (ref "C32") (pin "1") (pinfunction "1_1") (pintype "passive"))
      (node (ref "C33") (pin "1") (pinfunction "1_1") (pintype "passive"))
      (node (ref "C49") (pin "1") (pinfunction "1_1") (pintype "passive"))
      (node (ref "C50") (pin "1") (pinfunction "1_1") (pintype "passive"))
      (node (ref "FB3") (pin "2") (pinfunction "2_2") (pintype "passive"))
      (node (ref "R16") (pin "2") (pinfunction "2_2") (pintype "passive"))
      (node (ref "R17") (pin "1") (pinfunction "1_1") (pintype "passive"))
      (node (ref "R22") (pin "2") (pinfunction "2_2") (pintype "passive"))
      (node (ref "R23") (pin "2") (pinfunction "2_2") (pintype "passive"))
      (node (ref "R26") (pin "1") (pinfunction "1_1") (pintype "passive"))
      (node (ref "R27") (pin "1") (pinfunction "1_1") (pintype "passive"))
      (node (ref "U6") (pin "22") (pinfunction "VDD33_O_22") (pintype "passive"))
      (node (ref "U6") (pin "36") (pinfunction "VDD33_36") (pintype "passive"))
      (node (ref "U6") (pin "46") (pinfunction "VDD33_46") (pintype "passive"))
    )
    (net (code "197") (name "unconnected-(J3-NC-Pad4)") (class "Default")
      (node (ref "J3") (pin "4") (pinfunction "NC_4") (pintype "passive"))
    )
    (net (code "198") (name "unconnected-(K1-I{slash}O1-Pad1)") (class "Default")
      (node (ref "K1") (pin "1") (pinfunction "I/O1_1") (pintype "passive"))
    )
    (net (code "199") (name "unconnected-(K1-I{slash}O2-Pad4)") (class "Default")
      (node (ref "K1") (pin "4") (pinfunction "I/O2_4") (pintype "passive"))
    )
    (net (code "200") (name "unconnected-(P1-Pad2)") (class "Default")
      (node (ref "P1") (pin "2") (pinfunction "2_2") (pintype "passive"))
    )
    (net (code "201") (name "unconnected-(P1-Pad3)") (class "Default")
      (node (ref "P1") (pin "3") (pinfunction "3_3") (pintype "passive"))
    )
    (net (code "202") (name "unconnected-(P1-Pad6)") (class "Default")
      (node (ref "P1") (pin "6") (pinfunction "6_6") (pintype "passive"))
    )
    (net (code "203") (name "unconnected-(U1-PB1{slash}TIM1_CH3N{slash}TIM3_CH4{slash}TIM8_CH3N{slash}OTG_HS_INTN{slash}ETH_MII_RXD3{slash}ADC12_IN9-Pad47)") (class "Default")
      (node (ref "U1") (pin "47") (pinfunction "PB1/TIM1_CH3N/TIM3_CH4/TIM8_CH3N/OTG_HS_INTN/ETH_MII_RXD3/ADC12_IN9_47") (pintype "passive"))
    )
    (net (code "204") (name "unconnected-(U1-PB11{slash}TIM2_CH4{slash}U3_RX{slash}I2C2_SDA{slash}HS_ULPI_D4{slash}ETH_MII_TX_EN{slash}ETH_RMII_TX_EN-Pad70)") (class "Default")
      (node (ref "U1") (pin "70") (pinfunction "PB11/TIM2_CH4/U3_RX/I2C2_SDA/HS_ULPI_D4/ETH_MII_TX_EN/ETH_RMII_TX_EN_70") (pintype "passive"))
    )
    (net (code "205") (name "unconnected-(U1-PC0{slash}OTG_HS_ULPI_STP{slash}ADC123_IN10-Pad26)") (class "Default")
      (node (ref "U1") (pin "26") (pinfunction "PC0/OTG_HS_ULPI_STP/ADC123_IN10_26") (pintype "passive"))
    )
    (net (code "206") (name "unconnected-(U1-PC13{slash}RTC_AF1-Pad7)") (class "Default")
      (node (ref "U1") (pin "7") (pinfunction "PC13/RTC_AF1_7") (pintype "passive"))
    )
    (net (code "207") (name "unconnected-(U1-PC14-OSC32_IN-Pad8)") (class "Default")
      (node (ref "U1") (pin "8") (pinfunction "PC14-OSC32_IN_8") (pintype "passive"))
    )
    (net (code "208") (name "unconnected-(U1-PC15-OSC32_OUT-Pad9)") (class "Default")
      (node (ref "U1") (pin "9") (pinfunction "PC15-OSC32_OUT_9") (pintype "passive"))
    )
    (net (code "209") (name "unconnected-(U1-PD7{slash}FSMC_NE1{slash}FSMC_NCE2{slash}U2_CK-Pad123)") (class "Default")
      (node (ref "U1") (pin "123") (pinfunction "PD7/FSMC_NE1/FSMC_NCE2/U2_CK_123") (pintype "passive"))
    )
    (net (code "210") (name "unconnected-(U1-PD10{slash}FSMC_D15{slash}U3_CK-Pad79)") (class "Default")
      (node (ref "U1") (pin "79") (pinfunction "PD10/FSMC_D15/U3_CK_79") (pintype "passive"))
    )
    (net (code "211") (name "unconnected-(U1-PD11{slash}FSMC_A16{slash}FSMC_CLE{slash}U3_CTS-Pad80)") (class "Default")
      (node (ref "U1") (pin "80") (pinfunction "PD11/FSMC_A16/FSMC_CLE/U3_CTS_80") (pintype "passive"))
    )
    (net (code "212") (name "unconnected-(U1-PE2{slash}TRACECLK{slash}FSMC_A23{slash}ETH_MII_TXD3-Pad1)") (class "Default")
      (node (ref "U1") (pin "1") (pinfunction "PE2/TRACECLK/FSMC_A23/ETH_MII_TXD3_1") (pintype "passive"))
    )
    (net (code "213") (name "unconnected-(U1-PE3{slash}TRACED0{slash}FSMC_A19-Pad2)") (class "Default")
      (node (ref "U1") (pin "2") (pinfunction "PE3/TRACED0/FSMC_A19_2") (pintype "passive"))
    )
    (net (code "214") (name "unconnected-(U1-PE12{slash}FSMC_D9{slash}TIM1_CH3N-Pad65)") (class "Default")
      (node (ref "U1") (pin "65") (pinfunction "PE12/FSMC_D9/TIM1_CH3N_65") (pintype "passive"))
    )
    (net (code "215") (name "unconnected-(U1-PF11{slash}DCMI_D12-Pad49)") (class "Default")
      (node (ref "U1") (pin "49") (pinfunction "PF11/DCMI_D12_49") (pintype "passive"))
    )
    (net (code "216") (name "unconnected-(U1-PG2{slash}FSMC_A12-Pad87)") (class "Default")
      (node (ref "U1") (pin "87") (pinfunction "PG2/FSMC_A12_87") (pintype "passive"))
    )
    (net (code "217") (name "unconnected-(U1-PG3{slash}FSMC_A13-Pad88)") (class "Default")
      (node (ref "U1") (pin "88") (pinfunction "PG3/FSMC_A13_88") (pintype "passive"))
    )
    (net (code "218") (name "unconnected-(U1-PG4{slash}FSMC_A14-Pad89)") (class "Default")
      (node (ref "U1") (pin "89") (pinfunction "PG4/FSMC_A14_89") (pintype "passive"))
    )
    (net (code "219") (name "unconnected-(U1-PG5{slash}FSMC_A15-Pad90)") (class "Default")
      (node (ref "U1") (pin "90") (pinfunction "PG5/FSMC_A15_90") (pintype "passive"))
    )
    (net (code "220") (name "unconnected-(U1-PG6{slash}FSMC_INT2-Pad91)") (class "Default")
      (node (ref "U1") (pin "91") (pinfunction "PG6/FSMC_INT2_91") (pintype "passive"))
    )
    (net (code "221") (name "unconnected-(U1-PG7{slash}FSMC_INT3{slash}U6_CK-Pad92)") (class "Default")
      (node (ref "U1") (pin "92") (pinfunction "PG7/FSMC_INT3/U6_CK_92") (pintype "passive"))
    )
    (net (code "222") (name "unconnected-(U1-PG8{slash}U6_RTS{slash}ETH_PPS_OUT-Pad93)") (class "Default")
      (node (ref "U1") (pin "93") (pinfunction "PG8/U6_RTS/ETH_PPS_OUT_93") (pintype "passive"))
    )
    (net (code "223") (name "unconnected-(U1-PG9{slash}FSMC_NE2{slash}FSMC_NCE3{slash}U6_RX-Pad124)") (class "Default")
      (node (ref "U1") (pin "124") (pinfunction "PG9/FSMC_NE2/FSMC_NCE3/U6_RX_124") (pintype "passive"))
    )
    (net (code "224") (name "unconnected-(U1-PG12{slash}FSMC_NE4{slash}U6_RTS-Pad127)") (class "Default")
      (node (ref "U1") (pin "127") (pinfunction "PG12/FSMC_NE4/U6_RTS_127") (pintype "passive"))
    )
    (net (code "225") (name "unconnected-(U2-Vref-Pad5)") (class "Default")
      (node (ref "U2") (pin "5") (pinfunction "Vref_5") (pintype "passive"))
    )
    (net (code "226") (name "unconnected-(U4-Vref-Pad5)") (class "Default")
      (node (ref "U4") (pin "5") (pinfunction "Vref_5") (pintype "passive"))
    )
    (net (code "227") (name "unconnected-(U6-NC-Pad5)") (class "Default")
      (node (ref "U6") (pin "5") (pinfunction "NC_5") (pintype "passive"))
    )
    (net (code "228") (name "unconnected-(U6-NC-Pad6)") (class "Default")
      (node (ref "U6") (pin "6") (pinfunction "NC_6") (pintype "passive"))
    )
    (net (code "229") (name "unconnected-(U6-NC-Pad19)") (class "Default")
      (node (ref "U6") (pin "19") (pinfunction "NC_19") (pintype "passive"))
    )
    (net (code "230") (name "unconnected-(U6-NC-Pad30)") (class "Default")
      (node (ref "U6") (pin "30") (pinfunction "NC_30") (pintype "passive"))
    )
    (net (code "231") (name "unconnected-(U6-NC-Pad31)") (class "Default")
      (node (ref "U6") (pin "31") (pinfunction "NC_31") (pintype "passive"))
    )
    (net (code "232") (name "unconnected-(U6-NC-Pad32)") (class "Default")
      (node (ref "U6") (pin "32") (pinfunction "NC_32") (pintype "passive"))
    )
    (net (code "233") (name "unconnected-(U6-NC-Pad33)") (class "Default")
      (node (ref "U6") (pin "33") (pinfunction "NC_33") (pintype "passive"))
    )
    (net (code "234") (name "unconnected-(U6-NC-Pad34)") (class "Default")
      (node (ref "U6") (pin "34") (pinfunction "NC_34") (pintype "passive"))
    )
    (net (code "235") (name "unconnected-(U6-NC-Pad35)") (class "Default")
      (node (ref "U6") (pin "35") (pinfunction "NC_35") (pintype "passive"))
    )
    (net (code "236") (name "unconnected-(U6-NC-Pad38)") (class "Default")
      (node (ref "U6") (pin "38") (pinfunction "NC_38") (pintype "passive"))
    )
    (net (code "237") (name "unconnected-(U6-NC-Pad58)") (class "Default")
      (node (ref "U6") (pin "58") (pinfunction "NC_58") (pintype "passive"))
    )
    (net (code "238") (name "unconnected-(U6-NC-Pad61)") (class "Default")
      (node (ref "U6") (pin "61") (pinfunction "NC_61") (pintype "passive"))
    )
    (net (code "239") (name "unconnected-(U6-NC-Pad63)") (class "Default")
      (node (ref "U6") (pin "63") (pinfunction "NC_63") (pintype "passive"))
    )
    (net (code "240") (name "unconnected-(U7-DIN2-Pad10)") (class "Default")
      (node (ref "U7") (pin "10") (pinfunction "DIN2_10") (pintype "passive"))
    )
    (net (code "241") (name "unconnected-(U7-DOUT2-Pad7)") (class "Default")
      (node (ref "U7") (pin "7") (pinfunction "DOUT2_7") (pintype "passive"))
    )
    (net (code "242") (name "unconnected-(U7-RIN2-Pad8)") (class "Default")
      (node (ref "U7") (pin "8") (pinfunction "RIN2_8") (pintype "passive"))
    )
    (net (code "243") (name "unconnected-(U7-ROUT2-Pad9)") (class "Default")
      (node (ref "U7") (pin "9") (pinfunction "ROUT2_9") (pintype "passive"))
    )
    (net (code "244") (name "unconnected-(U11B-V+-Pad4)") (class "Default")
      (node (ref "U11") (pin "4") (pinfunction "V+_4") (pintype "power_in"))
    )
    (net (code "245") (name "unconnected-(U11B-V--Pad11)") (class "Default")
      (node (ref "U11") (pin "11") (pinfunction "V-_11") (pintype "power_in"))
    )
    (net (code "246") (name "unconnected-(U11C-V+-Pad4)") (class "Default")
      (node (ref "U11") (pin "4") (pinfunction "V+_4") (pintype "power_in"))
    )
    (net (code "247") (name "unconnected-(U11C-V--Pad11)") (class "Default")
      (node (ref "U11") (pin "11") (pinfunction "V-_11") (pintype "power_in"))
    )
  )
)
